# BLDC_MOTOR_TC264.net
KiCad netlist of a schematic drawn in Altium Designer
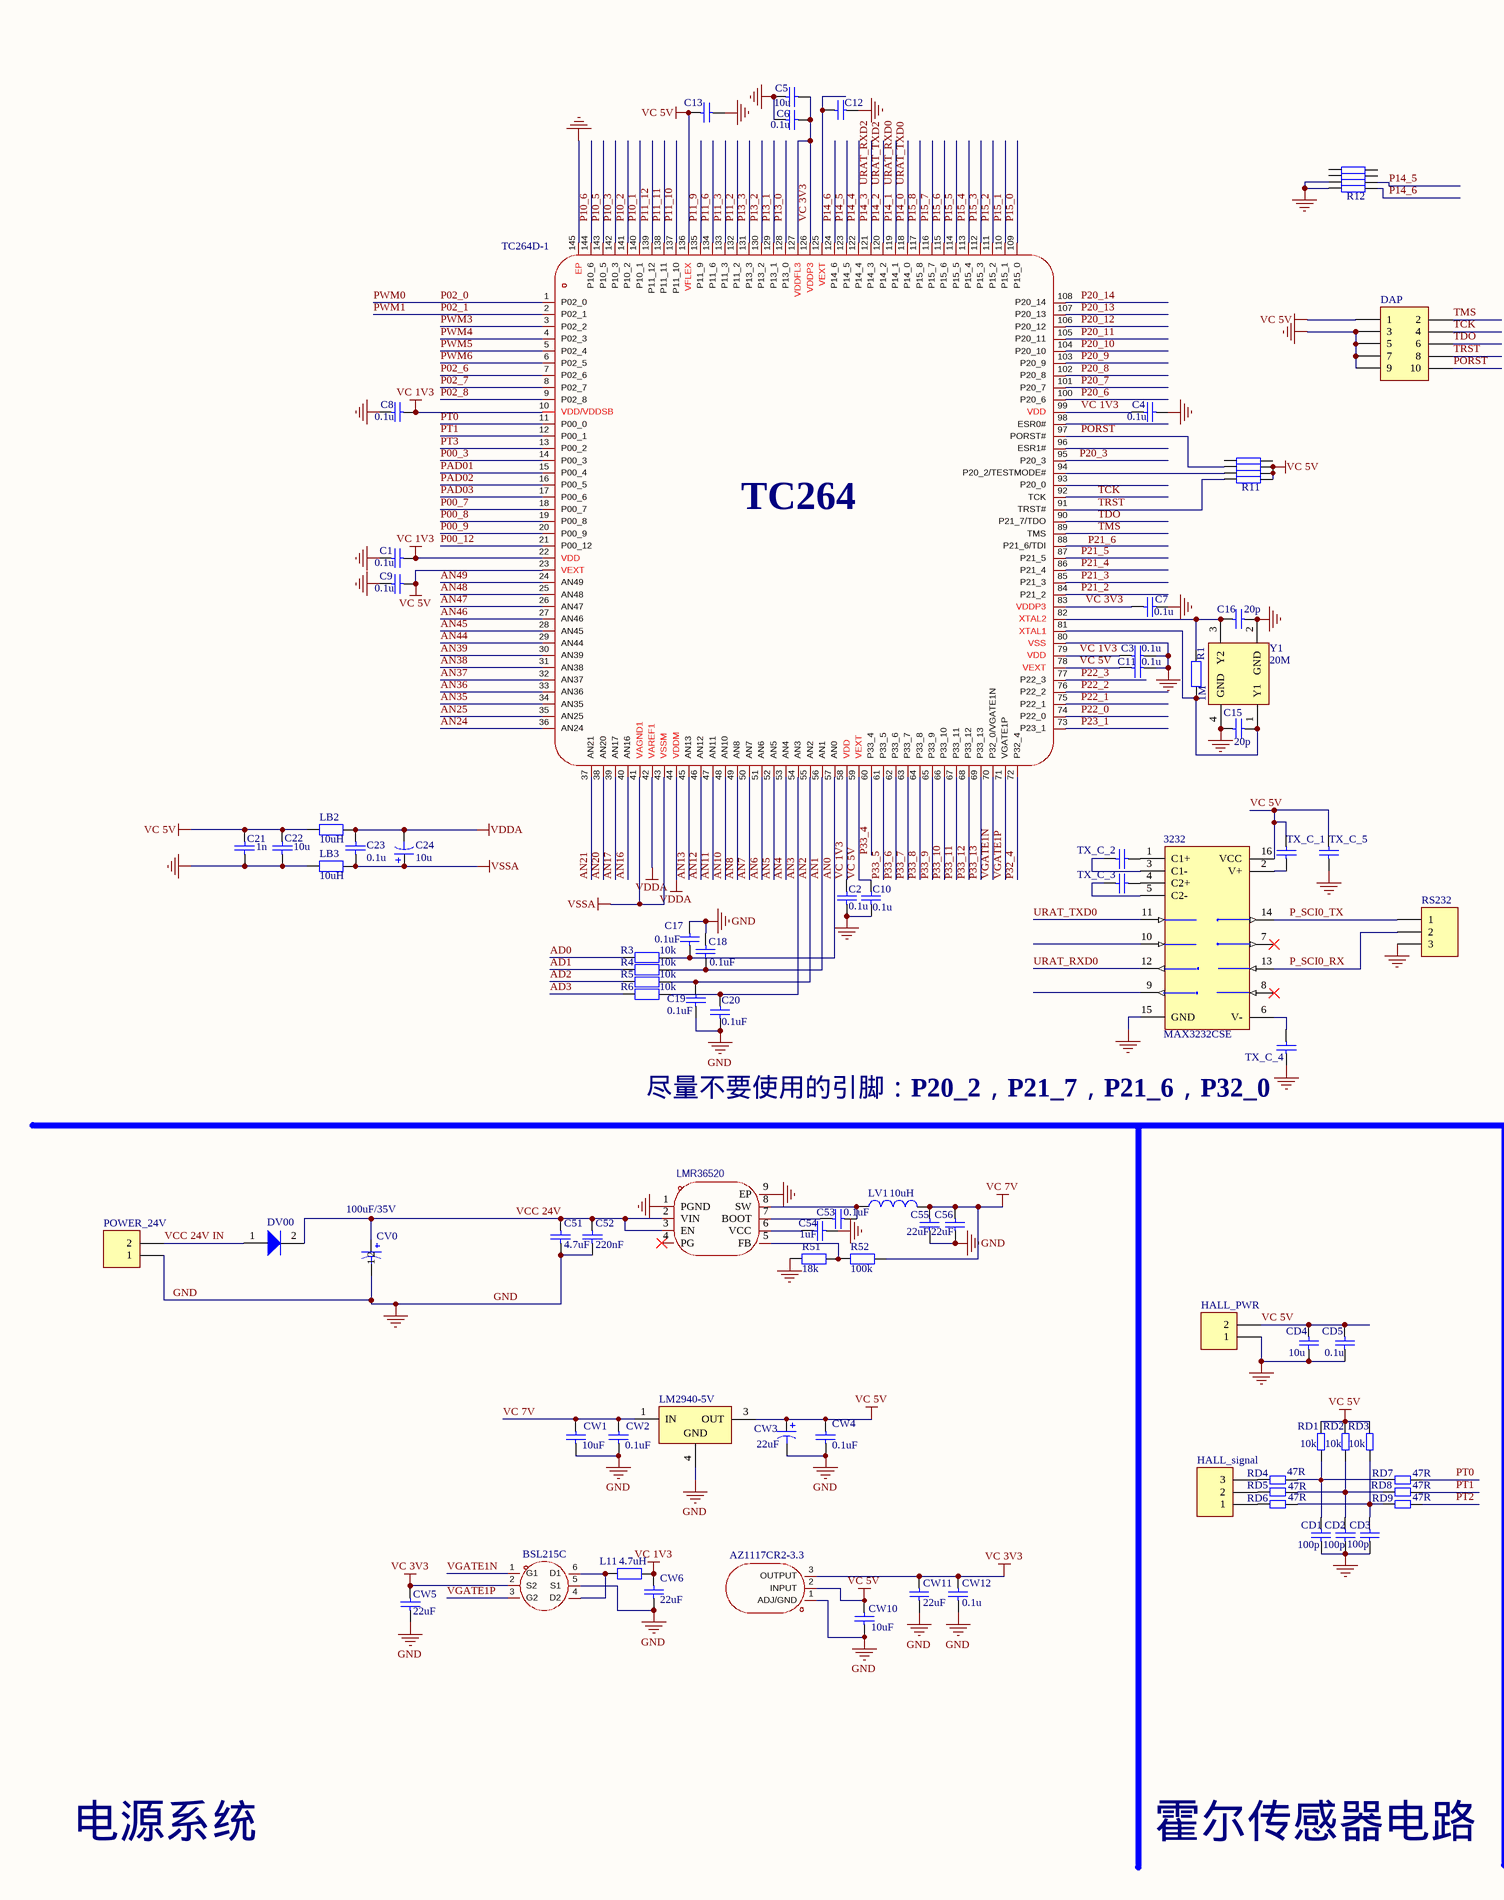
[diagram p0: BLDC_MOTOR_TC264.SCHDOC, left]
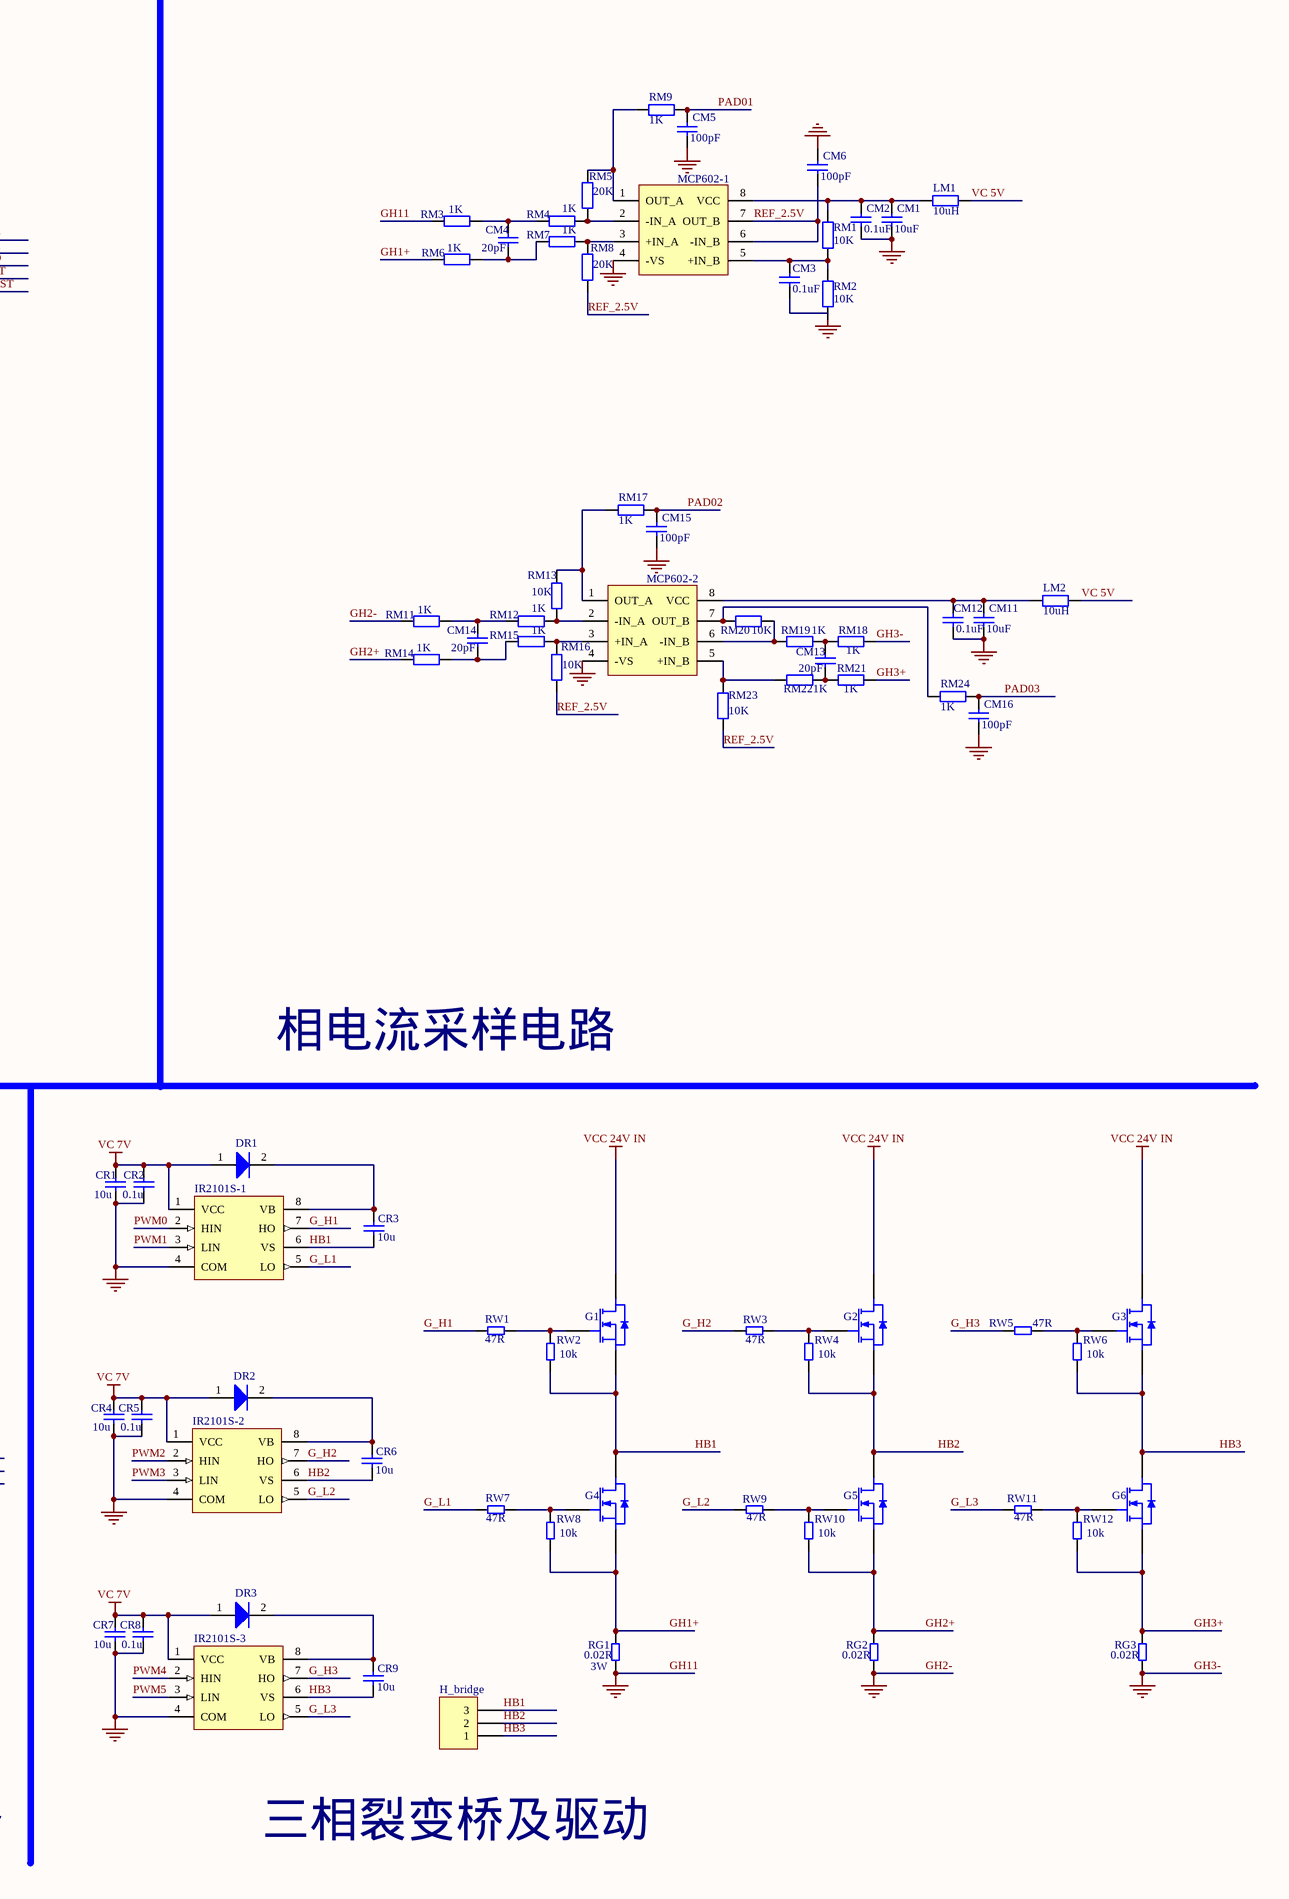
[diagram p1: BLDC_MOTOR_TC264.SCHDOC, right]

(export (version "E")
  (design (tool "Eeschema 10.0.6"))
  (components
    (comp (ref "3232")
      (value "MAX3232CSE")
      (footprint "LC-Standard-FootPrints-Protel99se-V1.01:LC-TSSOP-16")
      (description "3.0V TO 5.5V, Low-Power, up to 1Mbps, True RS-232 Transceiver Using Four 0.1礔 External Capacitor")
      (fields (field (name "PUBLISHER") "Altium Limited"))
      (libsource (lib "Maxim Communication Transceiver") (part "MAX3232CSE"))
    )
    (comp (ref "AZ1117CR2-3.3")
      (value "AZ1117CR2-3.3")
      (footprint "LC-SOT-89(SOT-89-3)")
      (libsource (lib "altium-import") (part "root_2_AZ1117CR2-3.3TRG1_"))
    )
    (comp (ref "BSL215C")
      (value "BSL215C")
      (footprint "LC-SOT-23-6")
      (libsource (lib "altium-import") (part "root_0_BSL215C_"))
    )
    (comp (ref "C1")
      (value "0.1u")
      (footprint "LC-0603_C")
      (description "Capacitor")
      (fields (field (name "PUBLISHER") "Altium Limited"))
      (libsource (lib "Miscellaneous Devices") (part "Cap"))
    )
    (comp (ref "C2")
      (value "0.1u")
      (footprint "LC-0603_C")
      (description "Capacitor")
      (fields (field (name "PUBLISHER") "Altium Limited"))
      (libsource (lib "Miscellaneous Devices") (part "Cap"))
    )
    (comp (ref "C3")
      (value "0.1u")
      (footprint "LC-0603_C")
      (description "Capacitor")
      (fields (field (name "PUBLISHER") "Altium Limited"))
      (libsource (lib "Miscellaneous Devices") (part "Cap"))
    )
    (comp (ref "C4")
      (value "0.1u")
      (footprint "LC-0603_C")
      (description "Capacitor")
      (fields (field (name "PUBLISHER") "Altium Limited"))
      (libsource (lib "Miscellaneous Devices") (part "Cap"))
    )
    (comp (ref "C5")
      (value "10u")
      (footprint "LC-0603_C")
      (description "Capacitor")
      (fields (field (name "PUBLISHER") "Altium Limited"))
      (libsource (lib "Miscellaneous Devices") (part "Cap"))
    )
    (comp (ref "C6")
      (value "0.1u")
      (footprint "LC-0603_C")
      (description "Capacitor")
      (fields (field (name "PUBLISHER") "Altium Limited"))
      (libsource (lib "Miscellaneous Devices") (part "Cap"))
    )
    (comp (ref "C7")
      (value "0.1u")
      (footprint "LC-0603_C")
      (description "Capacitor")
      (fields (field (name "PUBLISHER") "Altium Limited"))
      (libsource (lib "Miscellaneous Devices") (part "Cap"))
    )
    (comp (ref "C8")
      (value "0.1u")
      (footprint "LC-0603_C")
      (description "Capacitor")
      (fields (field (name "PUBLISHER") "Altium Limited"))
      (libsource (lib "Miscellaneous Devices") (part "Cap"))
    )
    (comp (ref "C9")
      (value "0.1u")
      (footprint "LC-0603_C")
      (description "Capacitor")
      (fields (field (name "PUBLISHER") "Altium Limited"))
      (libsource (lib "Miscellaneous Devices") (part "Cap"))
    )
    (comp (ref "C10")
      (value "0.1u")
      (footprint "LC-0603_C")
      (description "Capacitor")
      (fields (field (name "PUBLISHER") "Altium Limited"))
      (libsource (lib "Miscellaneous Devices") (part "Cap"))
    )
    (comp (ref "C11")
      (value "0.1u")
      (footprint "LC-0603_C")
      (description "Capacitor")
      (fields (field (name "PUBLISHER") "Altium Limited"))
      (libsource (lib "Miscellaneous Devices") (part "Cap"))
    )
    (comp (ref "C12")
      (value "0.1u")
      (footprint "LC-0603_C")
      (description "Capacitor")
      (fields (field (name "PUBLISHER") "Altium Limited"))
      (libsource (lib "Miscellaneous Devices") (part "Cap"))
    )
    (comp (ref "C13")
      (value "0.1u")
      (footprint "LC-0603_C")
      (description "Capacitor")
      (fields (field (name "PUBLISHER") "Altium Limited"))
      (libsource (lib "Miscellaneous Devices") (part "Cap"))
    )
    (comp (ref "C15")
      (value "20p")
      (footprint "LC-Standard-FootPrints-Protel99se-V1.01:LC-0603_C")
      (description "Capacitor")
      (fields (field (name "PUBLISHER") "Altium Limited"))
      (libsource (lib "Miscellaneous Devices") (part "Cap"))
    )
    (comp (ref "C16")
      (value "20p")
      (footprint "LC-Standard-FootPrints-Protel99se-V1.01:LC-0603_C")
      (description "Capacitor")
      (fields (field (name "PUBLISHER") "Altium Limited"))
      (libsource (lib "Miscellaneous Devices") (part "Cap"))
    )
    (comp (ref "C17")
      (value "0.1uF")
      (footprint "LC-Standard-FootPrints-Protel99se-V1.01:LC-0603_C")
      (description "Capacitor")
      (fields (field (name "PUBLISHER") "Altium Limited"))
      (libsource (lib "Miscellaneous Devices") (part "Cap"))
    )
    (comp (ref "C18")
      (value "0.1uF")
      (footprint "LC-Standard-FootPrints-Protel99se-V1.01:LC-0603_C")
      (description "Capacitor")
      (fields (field (name "PUBLISHER") "Altium Limited"))
      (libsource (lib "Miscellaneous Devices") (part "Cap"))
    )
    (comp (ref "C19")
      (value "0.1uF")
      (footprint "LC-Standard-FootPrints-Protel99se-V1.01:LC-0603_C")
      (description "Capacitor")
      (fields (field (name "PUBLISHER") "Altium Limited"))
      (libsource (lib "Miscellaneous Devices") (part "Cap"))
    )
    (comp (ref "C20")
      (value "0.1uF")
      (footprint "LC-Standard-FootPrints-Protel99se-V1.01:LC-0603_C")
      (description "Capacitor")
      (fields (field (name "PUBLISHER") "Altium Limited"))
      (libsource (lib "Miscellaneous Devices") (part "Cap"))
    )
    (comp (ref "C21")
      (value "1n")
      (footprint "LC-Standard-FootPrints-Protel99se-V1.01:LC-0603_C")
      (description "Capacitor")
      (fields (field (name "PUBLISHER") "Altium Limited"))
      (libsource (lib "Miscellaneous Devices") (part "Cap"))
    )
    (comp (ref "C22")
      (value "10u")
      (footprint "LC-Standard-FootPrints-Protel99se-V1.01:LC-0603_C")
      (description "Capacitor")
      (fields (field (name "PUBLISHER") "Altium Limited"))
      (libsource (lib "Miscellaneous Devices") (part "Cap"))
    )
    (comp (ref "C23")
      (value "0.1u")
      (footprint "LC-Standard-FootPrints-Protel99se-V1.01:LC-0603_C")
      (description "Capacitor")
      (fields (field (name "PUBLISHER") "Altium Limited"))
      (libsource (lib "Miscellaneous Devices") (part "Cap"))
    )
    (comp (ref "C24")
      (value "10u")
      (footprint "LC-0603_C")
      (description "Polarized Capacitor (Radial)")
      (fields (field (name "PUBLISHER") "Altium Limited"))
      (libsource (lib "Miscellaneous Devices") (part "Cap Pol1"))
    )
    (comp (ref "C51")
      (value "4.7uF")
      (footprint "LC-0805_C")
      (description "Capacitor")
      (fields (field (name "PUBLISHER") "Altium Limited"))
      (libsource (lib "Miscellaneous Devices") (part "Cap"))
    )
    (comp (ref "C52")
      (value "220nF")
      (footprint "LC-0805_C")
      (description "Capacitor")
      (fields (field (name "PUBLISHER") "Altium Limited"))
      (libsource (lib "Miscellaneous Devices") (part "Cap"))
    )
    (comp (ref "C53")
      (value "0.1uF")
      (footprint "LC-0603_C")
      (description "Capacitor")
      (fields (field (name "PUBLISHER") "Altium Limited"))
      (libsource (lib "Miscellaneous Devices") (part "Cap"))
    )
    (comp (ref "C54")
      (value "1uF")
      (footprint "LC-0603_C")
      (description "Capacitor")
      (fields (field (name "PUBLISHER") "Altium Limited"))
      (libsource (lib "Miscellaneous Devices") (part "Cap"))
    )
    (comp (ref "C55")
      (value "22uF")
      (footprint "LC-0805_C")
      (description "Capacitor")
      (fields (field (name "PUBLISHER") "Altium Limited"))
      (libsource (lib "Miscellaneous Devices") (part "Cap"))
    )
    (comp (ref "C56")
      (value "22uF")
      (footprint "LC-0805_C")
      (description "Capacitor")
      (fields (field (name "PUBLISHER") "Altium Limited"))
      (libsource (lib "Miscellaneous Devices") (part "Cap"))
    )
    (comp (ref "CD1")
      (value "100p")
      (footprint "LC-0805_C")
      (description "Capacitor")
      (fields (field (name "PUBLISHER") "Altium Limited"))
      (libsource (lib "Miscellaneous Devices") (part "Cap"))
    )
    (comp (ref "CD2")
      (value "100p")
      (footprint "LC-0805_C")
      (description "Capacitor")
      (fields (field (name "PUBLISHER") "Altium Limited"))
      (libsource (lib "Miscellaneous Devices") (part "Cap"))
    )
    (comp (ref "CD3")
      (value "100p")
      (footprint "LC-0805_C")
      (description "Capacitor")
      (fields (field (name "PUBLISHER") "Altium Limited"))
      (libsource (lib "Miscellaneous Devices") (part "Cap"))
    )
    (comp (ref "CD4")
      (value "10u")
      (footprint "LC-0805_C")
      (description "Capacitor")
      (fields (field (name "PUBLISHER") "Altium Limited"))
      (libsource (lib "Miscellaneous Devices") (part "Cap"))
    )
    (comp (ref "CD5")
      (value "0.1u")
      (footprint "LC-0805_C")
      (description "Capacitor")
      (fields (field (name "PUBLISHER") "Altium Limited"))
      (libsource (lib "Miscellaneous Devices") (part "Cap"))
    )
    (comp (ref "CM1")
      (value "10uF")
      (footprint "LC-0805_C")
      (description "Capacitor")
      (fields (field (name "Comment") "10u") (field (name "PUBLISHER") "Altium Limited"))
      (libsource (lib "Miscellaneous Devices") (part "Cap"))
    )
    (comp (ref "CM2")
      (value "0.1uF")
      (footprint "LC-0805_C")
      (description "Capacitor")
      (fields (field (name "Comment") "Cap") (field (name "PUBLISHER") "Altium Limited"))
      (libsource (lib "Miscellaneous Devices") (part "Cap"))
    )
    (comp (ref "CM3")
      (value "0.1uF")
      (footprint "0805")
      (description "Capacitor")
      (fields (field (name "Comment") "Cap") (field (name "PUBLISHER") "Altium Limited"))
      (libsource (lib "Miscellaneous Devices") (part "Cap"))
    )
    (comp (ref "CM4")
      (value "20pF")
      (footprint "LC-0805_C")
      (description "Capacitor")
      (fields (field (name "Comment") "Cap") (field (name "PUBLISHER") "Altium Limited"))
      (libsource (lib "Miscellaneous Devices") (part "Cap"))
    )
    (comp (ref "CM5")
      (value "100pF")
      (footprint "LC-0805_C")
      (description "Capacitor")
      (fields (field (name "Comment") "Cap") (field (name "PUBLISHER") "Altium Limited"))
      (libsource (lib "Miscellaneous Devices") (part "Cap"))
    )
    (comp (ref "CM6")
      (value "100pF")
      (footprint "LC-0805_C")
      (description "Capacitor")
      (fields (field (name "Comment") "Cap") (field (name "PUBLISHER") "Altium Limited"))
      (libsource (lib "Miscellaneous Devices") (part "Cap"))
    )
    (comp (ref "CM11")
      (value "10uF")
      (footprint "LC-0805_C")
      (description "Capacitor")
      (fields (field (name "Comment") "10u") (field (name "PUBLISHER") "Altium Limited"))
      (libsource (lib "Miscellaneous Devices") (part "Cap"))
    )
    (comp (ref "CM12")
      (value "0.1uF")
      (footprint "LC-0805_C")
      (description "Capacitor")
      (fields (field (name "Comment") "Cap") (field (name "PUBLISHER") "Altium Limited"))
      (libsource (lib "Miscellaneous Devices") (part "Cap"))
    )
    (comp (ref "CM13")
      (value "20pF")
      (footprint "LC-0805_C")
      (description "Capacitor")
      (fields (field (name "Comment") "Cap") (field (name "PUBLISHER") "Altium Limited"))
      (libsource (lib "Miscellaneous Devices") (part "Cap"))
    )
    (comp (ref "CM14")
      (value "20pF")
      (footprint "LC-0805_C")
      (description "Capacitor")
      (fields (field (name "Comment") "Cap") (field (name "PUBLISHER") "Altium Limited"))
      (libsource (lib "Miscellaneous Devices") (part "Cap"))
    )
    (comp (ref "CM15")
      (value "100pF")
      (footprint "LC-0805_C")
      (description "Capacitor")
      (fields (field (name "Comment") "Cap") (field (name "PUBLISHER") "Altium Limited"))
      (libsource (lib "Miscellaneous Devices") (part "Cap"))
    )
    (comp (ref "CM16")
      (value "100pF")
      (footprint "LC-0805_C")
      (description "Capacitor")
      (fields (field (name "PUBLISHER") "Altium Limited"))
      (libsource (lib "Miscellaneous Devices") (part "Cap"))
    )
    (comp (ref "CR1")
      (value "10u")
      (footprint "LC-0805_C")
      (description "Capacitor")
      (fields (field (name "PUBLISHER") "Altium Limited"))
      (libsource (lib "Miscellaneous Devices") (part "Cap"))
    )
    (comp (ref "CR2")
      (value "0.1u")
      (footprint "LC-0805_C")
      (description "Capacitor")
      (fields (field (name "PUBLISHER") "Altium Limited"))
      (libsource (lib "Miscellaneous Devices") (part "Cap"))
    )
    (comp (ref "CR3")
      (value "10u")
      (footprint "LC-1206_C")
      (description "Capacitor")
      (fields (field (name "PUBLISHER") "Altium Limited"))
      (libsource (lib "Miscellaneous Devices") (part "Cap"))
    )
    (comp (ref "CR4")
      (value "10u")
      (footprint "LC-0805_C")
      (description "Capacitor")
      (fields (field (name "PUBLISHER") "Altium Limited"))
      (libsource (lib "Miscellaneous Devices") (part "Cap"))
    )
    (comp (ref "CR5")
      (value "0.1u")
      (footprint "LC-0805_C")
      (description "Capacitor")
      (fields (field (name "PUBLISHER") "Altium Limited"))
      (libsource (lib "Miscellaneous Devices") (part "Cap"))
    )
    (comp (ref "CR6")
      (value "10u")
      (footprint "LC-1206_C")
      (description "Capacitor")
      (fields (field (name "PUBLISHER") "Altium Limited"))
      (libsource (lib "Miscellaneous Devices") (part "Cap"))
    )
    (comp (ref "CR7")
      (value "10u")
      (footprint "LC-0805_C")
      (description "Capacitor")
      (fields (field (name "PUBLISHER") "Altium Limited"))
      (libsource (lib "Miscellaneous Devices") (part "Cap"))
    )
    (comp (ref "CR8")
      (value "0.1u")
      (footprint "LC-0805_C")
      (description "Capacitor")
      (fields (field (name "PUBLISHER") "Altium Limited"))
      (libsource (lib "Miscellaneous Devices") (part "Cap"))
    )
    (comp (ref "CR9")
      (value "10u")
      (footprint "LC-1206_C")
      (description "Capacitor")
      (fields (field (name "PUBLISHER") "Altium Limited"))
      (libsource (lib "Miscellaneous Devices") (part "Cap"))
    )
    (comp (ref "CV0")
      (value "100uF/35V")
      (footprint "LIANGJICHAO_LIBRARY:CAP_SMD_8*10.2")
      (description "Polarized Capacitor (Radial)")
      (fields (field (name "Comment") "Cap Pol1") (field (name "PUBLISHER") "Altium Limited"))
      (libsource (lib "") (part "Cap Pol1_1"))
    )
    (comp (ref "CW1")
      (value "10uF")
      (footprint "LC-0603_C")
      (description "Capacitor")
      (fields (field (name "PUBLISHER") "Altium Limited"))
      (libsource (lib "Miscellaneous Devices") (part "Cap"))
    )
    (comp (ref "CW2")
      (value "0.1uF")
      (footprint "LC-0603_C")
      (description "Capacitor")
      (fields (field (name "Comment") "0.1u") (field (name "PUBLISHER") "Altium Limited"))
      (libsource (lib "Miscellaneous Devices") (part "Cap"))
    )
    (comp (ref "CW3")
      (value "22uF")
      (footprint "LC-0805_C")
      (description "Polarized Capacitor (Radial)")
      (fields (field (name "PUBLISHER") "Altium Limited"))
      (libsource (lib "Miscellaneous Devices") (part "Cap Pol1"))
    )
    (comp (ref "CW4")
      (value "0.1uF")
      (footprint "LC-0603_C")
      (description "Capacitor")
      (fields (field (name "Comment") "0.1u") (field (name "PUBLISHER") "Altium Limited"))
      (libsource (lib "Miscellaneous Devices") (part "Cap"))
    )
    (comp (ref "CW5")
      (value "22uF")
      (footprint "LC-0603_C")
      (description "Capacitor")
      (fields (field (name "PUBLISHER") "Altium Limited"))
      (libsource (lib "Miscellaneous Devices") (part "Cap"))
    )
    (comp (ref "CW6")
      (value "22uF")
      (footprint "LC-0603_C")
      (description "Capacitor")
      (fields (field (name "PUBLISHER") "Altium Limited"))
      (libsource (lib "Miscellaneous Devices") (part "Cap"))
    )
    (comp (ref "CW10")
      (value "10uF")
      (footprint "LC-0603_C")
      (description "Capacitor")
      (fields (field (name "PUBLISHER") "Altium Limited"))
      (libsource (lib "Miscellaneous Devices") (part "Cap"))
    )
    (comp (ref "CW11")
      (value "22uF")
      (footprint "LC-0603_C")
      (description "Capacitor")
      (fields (field (name "PUBLISHER") "Altium Limited"))
      (libsource (lib "Miscellaneous Devices") (part "Cap"))
    )
    (comp (ref "CW12")
      (value "0.1u")
      (footprint "LC-0603_C")
      (description "Capacitor")
      (fields (field (name "PUBLISHER") "Altium Limited"))
      (libsource (lib "Miscellaneous Devices") (part "Cap"))
    )
    (comp (ref "DAP")
      (value "Header 5X2")
      (footprint "HDR2X5")
      (description "Header, 5-Pin, Dual row")
      (fields (field (name "PUBLISHER") "Altium Limited"))
      (libsource (lib "Miscellaneous Connectors") (part "Header 5X2"))
    )
    (comp (ref "DR1")
      (value "C84635")
      (footprint "LC-SMA(DO-214AC)_S2")
      (description "Default Diode")
      (fields (field (name "PUBLISHER") "Altium Limited"))
      (libsource (lib "Miscellaneous Devices") (part "Diode"))
    )
    (comp (ref "DR2")
      (value "C84635")
      (footprint "LC-SMA(DO-214AC)_S2")
      (description "Default Diode")
      (fields (field (name "PUBLISHER") "Altium Limited"))
      (libsource (lib "Miscellaneous Devices") (part "Diode"))
    )
    (comp (ref "DR3")
      (value "C84635")
      (footprint "LC-SMA(DO-214AC)_S2")
      (description "Default Diode")
      (fields (field (name "PUBLISHER") "Altium Limited"))
      (libsource (lib "Miscellaneous Devices") (part "Diode"))
    )
    (comp (ref "DV00")
      (value "C35722")
      (footprint "LC-SMA(DO-214AC)_S5")
      (description "Default Diode")
      (fields (field (name "PUBLISHER") "Altium Limited"))
      (libsource (lib "Miscellaneous Devices") (part "Diode"))
    )
    (comp (ref "G1") (value "BUK9222") (footprint "TO-252-2") (libsource (lib "liang_SCH") (part "MOSFET_N")))
    (comp (ref "G2") (value "BUK9222") (footprint "TO-252-2") (libsource (lib "liang_SCH") (part "MOSFET_N")))
    (comp (ref "G3") (value "BUK9222") (footprint "TO-252-2") (libsource (lib "liang_SCH") (part "MOSFET_N")))
    (comp (ref "G4") (value "BUK9222") (footprint "TO-252-2") (libsource (lib "liang_SCH") (part "MOSFET_N")))
    (comp (ref "G5") (value "BUK9222") (footprint "TO-252-2") (libsource (lib "liang_SCH") (part "MOSFET_N")))
    (comp (ref "G6") (value "BUK9222") (footprint "TO-252-2") (libsource (lib "liang_SCH") (part "MOSFET_N")))
    (comp (ref "HALL_PWR")
      (value "~")
      (footprint "KF128-jiexian_2P")
      (description "Header, 2-Pin")
      (fields (field (name "PUBLISHER") "Altium Limited"))
      (libsource (lib "Miscellaneous Connectors") (part "Header 2"))
    )
    (comp (ref "HALL_signal")
      (value "Header 3")
      (footprint "kf128_duanzi_3P")
      (description "Header, 3-Pin")
      (fields (field (name "PUBLISHER") "Altium Limited"))
      (libsource (lib "") (part "Header 3_1"))
    )
    (comp (ref "H_bridge")
      (value "Header 3")
      (footprint "kf128_duanzi_3P")
      (description "Header, 3-Pin")
      (fields (field (name "PUBLISHER") "Altium Limited"))
      (libsource (lib "") (part "Header 3_1"))
    )
    (comp (ref "IR2101S-1")
      (value "IR2101")
      (footprint "LC-SOIC-8_150mil")
      (libsource (lib "liang_SCH") (part "IR2101"))
    )
    (comp (ref "IR2101S-2")
      (value "IR2101")
      (footprint "LC-SOIC-8_150mil")
      (libsource (lib "liang_SCH") (part "IR2101"))
    )
    (comp (ref "IR2101S-3")
      (value "IR2101")
      (footprint "LC-SOIC-8_150mil")
      (libsource (lib "liang_SCH") (part "IR2101"))
    )
    (comp (ref "L11")
      (value "4.7uH")
      (footprint "LIANGJICHAO_LIBRARY:L0806")
      (description "Resistor")
      (fields (field (name "PUBLISHER") "Altium Limited"))
      (libsource (lib "") (part "Res2_3"))
    )
    (comp (ref "LB2")
      (value "10uH")
      (footprint "LC-Standard-FootPrints-Protel99se-V1.01:LC-1206_L")
      (description "Resistor")
      (fields (field (name "Comment") "C1051") (field (name "PUBLISHER") "Altium Limited"))
      (libsource (lib "") (part "Res2_1"))
    )
    (comp (ref "LB3")
      (value "10uH")
      (footprint "LC-Standard-FootPrints-Protel99se-V1.01:LC-1206_L")
      (description "Resistor")
      (fields (field (name "Comment") "C1051") (field (name "PUBLISHER") "Altium Limited"))
      (libsource (lib "") (part "Res2_1"))
    )
    (comp (ref "LM1")
      (value "10uH")
      (footprint "LC-0805_L")
      (description "Resistor")
      (fields (field (name "PUBLISHER") "Altium Limited"))
      (libsource (lib "") (part "Res2_1"))
    )
    (comp (ref "LM2")
      (value "10uH")
      (footprint "LC-0805_L")
      (description "Resistor")
      (fields (field (name "PUBLISHER") "Altium Limited"))
      (libsource (lib "") (part "Res2_1"))
    )
    (comp (ref "LM2940-5V")
      (value "LM2940")
      (footprint "LC-SOT-223")
      (description "Precision 1A Regulator")
      (fields (field (name "PUBLISHER") "Altium Limited"))
      (libsource (lib "ST Power Mgt Voltage Regulator") (part "L7805ABD2T"))
    )
    (comp (ref "LMR36520")
      (value "LMR36520FADDAR")
      (footprint "LC-SOIC-8_EP_150mil")
      (fields (field (name "MANUFACTURER") "TI(德州仪器)"))
      (libsource (lib "altium-import") (part "root_0_LMR36520FADDAR_"))
    )
    (comp (ref "LV1")
      (value "10uH")
      (footprint "LIANGJICHAO_LIBRARY:SMD_0650")
      (description "Inductor")
      (fields (field (name "PUBLISHER") "Altium Limited"))
      (libsource (lib "Miscellaneous Devices") (part "Inductor"))
    )
    (comp (ref "MCP602-1")
      (value "LM258")
      (footprint "SOP8_555_lm393")
      (libsource (lib "liang_SCH") (part "LM258"))
    )
    (comp (ref "MCP602-2")
      (value "LM258")
      (footprint "SOP8_555_lm393")
      (libsource (lib "liang_SCH") (part "LM258"))
    )
    (comp (ref "POWER_24V")
      (value "Header 2")
      (footprint "KF128-jiexian_2P")
      (description "Header, 2-Pin")
      (fields (field (name "PUBLISHER") "Altium Limited"))
      (libsource (lib "Miscellaneous Connectors") (part "Header 2"))
    )
    (comp (ref "R1")
      (value "1M")
      (footprint "LC-Standard-FootPrints-Protel99se-V1.01:LC-0603_R")
      (description "Resistor")
      (fields (field (name "PUBLISHER") "Altium Limited"))
      (libsource (lib "") (part "Res2_2"))
    )
    (comp (ref "R3")
      (value "10k")
      (footprint "LC-Standard-FootPrints-Protel99se-V1.01:LC-0603_R")
      (description "Resistor")
      (fields (field (name "PUBLISHER") "Altium Limited"))
      (libsource (lib "") (part "Res2_3"))
    )
    (comp (ref "R4")
      (value "10k")
      (footprint "LC-Standard-FootPrints-Protel99se-V1.01:LC-0603_R")
      (description "Resistor")
      (fields (field (name "PUBLISHER") "Altium Limited"))
      (libsource (lib "") (part "Res2_3"))
    )
    (comp (ref "R5")
      (value "10k")
      (footprint "LC-Standard-FootPrints-Protel99se-V1.01:LC-0603_R")
      (description "Resistor")
      (fields (field (name "PUBLISHER") "Altium Limited"))
      (libsource (lib "") (part "Res2_3"))
    )
    (comp (ref "R6")
      (value "10k")
      (footprint "LC-Standard-FootPrints-Protel99se-V1.01:LC-0603_R")
      (description "Resistor")
      (fields (field (name "PUBLISHER") "Altium Limited"))
      (libsource (lib "") (part "Res2_3"))
    )
    (comp (ref "R11")
      (value "10k")
      (footprint "LC-0603_Rx4")
      (libsource (lib "liang_SCH") (part "RES_RANGE_4"))
    )
    (comp (ref "R12")
      (value "47k")
      (footprint "LC-0603_Rx4")
      (libsource (lib "liang_SCH") (part "RES_RANGE_4"))
    )
    (comp (ref "R51")
      (value "18k")
      (footprint "LC-0603_R")
      (description "Resistor")
      (fields (field (name "PUBLISHER") "Altium Limited"))
      (libsource (lib "") (part "Res2_1"))
    )
    (comp (ref "R52")
      (value "100k")
      (footprint "LC-0603_R")
      (description "Resistor")
      (fields (field (name "PUBLISHER") "Altium Limited"))
      (libsource (lib "") (part "Res2_1"))
    )
    (comp (ref "RD1") (value "10k") (footprint "LC-0805_R") (libsource (lib "") (part "RES_COMMOM_2")))
    (comp (ref "RD2") (value "10k") (footprint "LC-0805_R") (libsource (lib "") (part "RES_COMMOM_2")))
    (comp (ref "RD3")
      (value "10k")
      (footprint "LC-Standard-FootPrints-Protel99se-V1.01:LC-0805_R")
      (libsource (lib "") (part "RES_COMMOM_2"))
    )
    (comp (ref "RD4") (value "47R") (footprint "LC-0805_R") (libsource (lib "liang_SCH") (part "RES_COMMOM")))
    (comp (ref "RD5") (value "47R") (footprint "LC-0805_R") (libsource (lib "liang_SCH") (part "RES_COMMOM")))
    (comp (ref "RD6")
      (value "47R")
      (footprint "LC-Standard-FootPrints-Protel99se-V1.01:LC-0805_R")
      (libsource (lib "liang_SCH") (part "RES_COMMOM"))
    )
    (comp (ref "RD7") (value "47R") (footprint "LC-0805_R") (libsource (lib "liang_SCH") (part "RES_COMMOM")))
    (comp (ref "RD8") (value "47R") (footprint "LC-0805_R") (libsource (lib "liang_SCH") (part "RES_COMMOM")))
    (comp (ref "RD9")
      (value "47R")
      (footprint "LC-Standard-FootPrints-Protel99se-V1.01:LC-0805_R")
      (libsource (lib "liang_SCH") (part "RES_COMMOM"))
    )
    (comp (ref "RG1")
      (value "0.02R")
      (footprint "LC-Standard-FootPrints-Protel99se-V1.01:LC-2512_R")
      (libsource (lib "") (part "RES_COMMOM_2"))
    )
    (comp (ref "RG2")
      (value "0.02R")
      (footprint "LC-Standard-FootPrints-Protel99se-V1.01:LC-2512_R")
      (libsource (lib "") (part "RES_COMMOM_2"))
    )
    (comp (ref "RG3")
      (value "0.02R")
      (footprint "LC-Standard-FootPrints-Protel99se-V1.01:LC-2512_R")
      (libsource (lib "") (part "RES_COMMOM_2"))
    )
    (comp (ref "RM1")
      (value "10K")
      (footprint "LC-0805_R")
      (description "Resistor")
      (fields (field (name "Comment") "Res2") (field (name "PUBLISHER") "Altium Limited"))
      (libsource (lib "") (part "Res2_2"))
    )
    (comp (ref "RM2")
      (value "10K")
      (footprint "LC-0805_R")
      (description "Resistor")
      (fields (field (name "Comment") "Res2") (field (name "PUBLISHER") "Altium Limited"))
      (libsource (lib "") (part "Res2_2"))
    )
    (comp (ref "RM3")
      (value "1K")
      (footprint "LC-0805_R")
      (description "Resistor")
      (fields (field (name "Comment") "Res2") (field (name "PUBLISHER") "Altium Limited"))
      (libsource (lib "") (part "Res2_1"))
    )
    (comp (ref "RM4")
      (value "1K")
      (footprint "LC-0805_R")
      (description "Resistor")
      (fields (field (name "Comment") "Res2") (field (name "PUBLISHER") "Altium Limited"))
      (libsource (lib "") (part "Res2_1"))
    )
    (comp (ref "RM5")
      (value "20K")
      (footprint "LC-0805_R")
      (description "Resistor")
      (fields (field (name "Comment") "Res2") (field (name "PUBLISHER") "Altium Limited"))
      (libsource (lib "Miscellaneous Devices") (part "Res2"))
    )
    (comp (ref "RM6")
      (value "1K")
      (footprint "LC-0805_R")
      (description "Resistor")
      (fields (field (name "Comment") "Res2") (field (name "PUBLISHER") "Altium Limited"))
      (libsource (lib "") (part "Res2_1"))
    )
    (comp (ref "RM7")
      (value "1K")
      (footprint "LC-0805_R")
      (description "Resistor")
      (fields (field (name "Comment") "Res2") (field (name "PUBLISHER") "Altium Limited"))
      (libsource (lib "") (part "Res2_1"))
    )
    (comp (ref "RM8")
      (value "20K")
      (footprint "LC-0805_R")
      (description "Resistor")
      (fields (field (name "Comment") "Res2") (field (name "PUBLISHER") "Altium Limited"))
      (libsource (lib "") (part "Res2_2"))
    )
    (comp (ref "RM9")
      (value "1K")
      (footprint "LC-0805_R")
      (description "Resistor")
      (fields (field (name "Comment") "Res2") (field (name "PUBLISHER") "Altium Limited"))
      (libsource (lib "") (part "Res2_1"))
    )
    (comp (ref "RM11")
      (value "1K")
      (footprint "LC-0805_R")
      (description "Resistor")
      (fields (field (name "Comment") "Res2") (field (name "PUBLISHER") "Altium Limited"))
      (libsource (lib "") (part "Res2_1"))
    )
    (comp (ref "RM12")
      (value "1K")
      (footprint "LC-0805_R")
      (description "Resistor")
      (fields (field (name "Comment") "Res2") (field (name "PUBLISHER") "Altium Limited"))
      (libsource (lib "") (part "Res2_1"))
    )
    (comp (ref "RM13")
      (value "10K")
      (footprint "LC-0805_R")
      (description "Resistor")
      (fields (field (name "Comment") "Res2") (field (name "PUBLISHER") "Altium Limited"))
      (libsource (lib "Miscellaneous Devices") (part "Res2"))
    )
    (comp (ref "RM14")
      (value "1K")
      (footprint "LC-0805_R")
      (description "Resistor")
      (fields (field (name "Comment") "Res2") (field (name "PUBLISHER") "Altium Limited"))
      (libsource (lib "") (part "Res2_1"))
    )
    (comp (ref "RM15")
      (value "1K")
      (footprint "LC-0805_R")
      (description "Resistor")
      (fields (field (name "Comment") "Res2") (field (name "PUBLISHER") "Altium Limited"))
      (libsource (lib "") (part "Res2_1"))
    )
    (comp (ref "RM16")
      (value "10K")
      (footprint "LC-0805_R")
      (description "Resistor")
      (fields (field (name "Comment") "Res2") (field (name "PUBLISHER") "Altium Limited"))
      (libsource (lib "") (part "Res2_2"))
    )
    (comp (ref "RM17")
      (value "1K")
      (footprint "LC-0805_R")
      (description "Resistor")
      (fields (field (name "Comment") "Res2") (field (name "PUBLISHER") "Altium Limited"))
      (libsource (lib "") (part "Res2_1"))
    )
    (comp (ref "RM18")
      (value "1K")
      (footprint "LC-0805_R")
      (description "Resistor")
      (fields (field (name "Comment") "Res2") (field (name "PUBLISHER") "Altium Limited"))
      (libsource (lib "") (part "Res2_3"))
    )
    (comp (ref "RM19")
      (value "1K")
      (footprint "LC-0805_R")
      (description "Resistor")
      (fields (field (name "Comment") "Res2") (field (name "PUBLISHER") "Altium Limited"))
      (libsource (lib "") (part "Res2_3"))
    )
    (comp (ref "RM20")
      (value "10K")
      (footprint "LC-0805_R")
      (description "Resistor")
      (fields (field (name "Comment") "Res2") (field (name "PUBLISHER") "Altium Limited"))
      (libsource (lib "") (part "Res2_1"))
    )
    (comp (ref "RM21")
      (value "1K")
      (footprint "LC-0805_R")
      (description "Resistor")
      (fields (field (name "Comment") "Res2") (field (name "PUBLISHER") "Altium Limited"))
      (libsource (lib "") (part "Res2_3"))
    )
    (comp (ref "RM22")
      (value "1K")
      (footprint "LC-0805_R")
      (description "Resistor")
      (fields (field (name "Comment") "Res2") (field (name "PUBLISHER") "Altium Limited"))
      (libsource (lib "") (part "Res2_3"))
    )
    (comp (ref "RM23")
      (value "10K")
      (footprint "LC-0805_R")
      (description "Resistor")
      (fields (field (name "Comment") "Res2") (field (name "PUBLISHER") "Altium Limited"))
      (libsource (lib "Miscellaneous Devices") (part "Res2"))
    )
    (comp (ref "RM24")
      (value "1K")
      (footprint "LC-0805_R")
      (description "Resistor")
      (fields (field (name "Comment") "Res2") (field (name "PUBLISHER") "Altium Limited"))
      (libsource (lib "") (part "Res2_1"))
    )
    (comp (ref "RS232")
      (value "Header 3")
      (footprint "kf128_duanzi_3P")
      (description "Header, 3-Pin")
      (fields (field (name "PUBLISHER") "Altium Limited"))
      (libsource (lib "Miscellaneous Connectors") (part "Header 3"))
    )
    (comp (ref "RW1") (value "47R") (footprint "0805") (libsource (lib "liang_SCH") (part "RES_COMMOM")))
    (comp (ref "RW2") (value "10k") (footprint "0805") (libsource (lib "") (part "RES_COMMOM_1")))
    (comp (ref "RW3") (value "47R") (footprint "0805") (libsource (lib "liang_SCH") (part "RES_COMMOM")))
    (comp (ref "RW4") (value "10k") (footprint "0805") (libsource (lib "") (part "RES_COMMOM_1")))
    (comp (ref "RW5") (value "47R") (footprint "0805") (libsource (lib "liang_SCH") (part "RES_COMMOM")))
    (comp (ref "RW6") (value "10k") (footprint "0805") (libsource (lib "") (part "RES_COMMOM_1")))
    (comp (ref "RW7") (value "47R") (footprint "0805") (libsource (lib "liang_SCH") (part "RES_COMMOM")))
    (comp (ref "RW8") (value "10k") (footprint "0805") (libsource (lib "") (part "RES_COMMOM_1")))
    (comp (ref "RW9") (value "47R") (footprint "0805") (libsource (lib "liang_SCH") (part "RES_COMMOM")))
    (comp (ref "RW10") (value "10k") (footprint "0805") (libsource (lib "") (part "RES_COMMOM_1")))
    (comp (ref "RW11") (value "47R") (footprint "0805") (libsource (lib "liang_SCH") (part "RES_COMMOM")))
    (comp (ref "RW12") (value "10k") (footprint "0805") (libsource (lib "") (part "RES_COMMOM_1")))
    (comp (ref "TC264D-1")
      (value "TC264D")
      (footprint "TC264D-LQFP144")
      (libsource (lib "liang_SCH") (part "TC264D"))
    )
    (comp (ref "TX_C_1")
      (value "0.1u")
      (footprint "LC-0603_C")
      (description "Capacitor")
      (fields (field (name "PUBLISHER") "Altium Limited"))
      (libsource (lib "Miscellaneous Devices") (part "Cap"))
    )
    (comp (ref "TX_C_2")
      (value "0.1u")
      (footprint "LC-Standard-FootPrints-Protel99se-V1.01:LC-0603_C")
      (description "Capacitor")
      (fields (field (name "PUBLISHER") "Altium Limited"))
      (libsource (lib "Miscellaneous Devices") (part "Cap"))
    )
    (comp (ref "TX_C_3")
      (value "0.1u")
      (footprint "LC-Standard-FootPrints-Protel99se-V1.01:LC-0603_C")
      (description "Capacitor")
      (fields (field (name "PUBLISHER") "Altium Limited"))
      (libsource (lib "Miscellaneous Devices") (part "Cap"))
    )
    (comp (ref "TX_C_4")
      (value "0.1u")
      (footprint "LC-Standard-FootPrints-Protel99se-V1.01:LC-0603_C")
      (description "Capacitor")
      (fields (field (name "PUBLISHER") "Altium Limited"))
      (libsource (lib "Miscellaneous Devices") (part "Cap"))
    )
    (comp (ref "TX_C_5")
      (value "0.1u")
      (footprint "LC-0603_C")
      (description "Capacitor")
      (fields (field (name "PUBLISHER") "Altium Limited"))
      (libsource (lib "Miscellaneous Devices") (part "Cap"))
    )
    (comp (ref "Y1")
      (value "20M")
      (footprint "LC-Standard-FootPrints-Protel99se-V1.01:LC-SMD-3225_4P")
      (libsource (lib "liang_SCH") (part "XTL-YXL"))
    )
  )
  (nets
    (net (code "1") (name "/AD0") (class "Default")
      (node (ref "R3") (pin "1") (pinfunction "1_1") (pintype "passive"))
    )
    (net (code "2") (name "/AD1") (class "Default")
      (node (ref "R4") (pin "1") (pinfunction "1_1") (pintype "passive"))
    )
    (net (code "3") (name "/AD2") (class "Default")
      (node (ref "R5") (pin "1") (pinfunction "1_1") (pintype "passive"))
    )
    (net (code "4") (name "/AD3") (class "Default")
      (node (ref "R6") (pin "1") (pinfunction "1_1") (pintype "passive"))
    )
    (net (code "5") (name "/AN0") (class "Default")
      (node (ref "C17") (pin "1") (pinfunction "1_1") (pintype "passive"))
      (node (ref "R3") (pin "2") (pinfunction "2_2") (pintype "passive"))
      (node (ref "TC264D-1") (pin "57") (pinfunction "AN0_57") (pintype "passive"))
    )
    (net (code "6") (name "/AN1") (class "Default")
      (node (ref "C18") (pin "1") (pinfunction "1_1") (pintype "passive"))
      (node (ref "R4") (pin "2") (pinfunction "2_2") (pintype "passive"))
      (node (ref "TC264D-1") (pin "56") (pinfunction "AN1_56") (pintype "passive"))
    )
    (net (code "7") (name "/AN2") (class "Default")
      (node (ref "C19") (pin "2") (pinfunction "2_2") (pintype "passive"))
      (node (ref "R5") (pin "2") (pinfunction "2_2") (pintype "passive"))
      (node (ref "TC264D-1") (pin "55") (pinfunction "AN2_55") (pintype "passive"))
    )
    (net (code "8") (name "/AN3") (class "Default")
      (node (ref "C20") (pin "2") (pinfunction "2_2") (pintype "passive"))
      (node (ref "R6") (pin "2") (pinfunction "2_2") (pintype "passive"))
      (node (ref "TC264D-1") (pin "54") (pinfunction "AN3_54") (pintype "passive"))
    )
    (net (code "9") (name "/AN4") (class "Default")
      (node (ref "TC264D-1") (pin "53") (pinfunction "AN4_53") (pintype "passive"))
    )
    (net (code "10") (name "/AN5") (class "Default")
      (node (ref "TC264D-1") (pin "52") (pinfunction "AN5_52") (pintype "passive"))
    )
    (net (code "11") (name "/AN6") (class "Default")
      (node (ref "TC264D-1") (pin "51") (pinfunction "AN6_51") (pintype "passive"))
    )
    (net (code "12") (name "/AN7") (class "Default")
      (node (ref "TC264D-1") (pin "50") (pinfunction "AN7_50") (pintype "passive"))
    )
    (net (code "13") (name "/AN8") (class "Default")
      (node (ref "TC264D-1") (pin "49") (pinfunction "AN8_49") (pintype "passive"))
    )
    (net (code "14") (name "/AN10") (class "Default")
      (node (ref "TC264D-1") (pin "48") (pinfunction "AN10_48") (pintype "passive"))
    )
    (net (code "15") (name "/AN11") (class "Default")
      (node (ref "TC264D-1") (pin "47") (pinfunction "AN11_47") (pintype "passive"))
    )
    (net (code "16") (name "/AN12") (class "Default")
      (node (ref "TC264D-1") (pin "46") (pinfunction "AN12_46") (pintype "passive"))
    )
    (net (code "17") (name "/AN13") (class "Default")
      (node (ref "TC264D-1") (pin "45") (pinfunction "AN13_45") (pintype "passive"))
    )
    (net (code "18") (name "/AN16") (class "Default")
      (node (ref "TC264D-1") (pin "40") (pinfunction "AN16_40") (pintype "passive"))
    )
    (net (code "19") (name "/AN17") (class "Default")
      (node (ref "TC264D-1") (pin "39") (pinfunction "AN17_39") (pintype "passive"))
    )
    (net (code "20") (name "/AN20") (class "Default")
      (node (ref "TC264D-1") (pin "38") (pinfunction "AN20_38") (pintype "passive"))
    )
    (net (code "21") (name "/AN21") (class "Default")
      (node (ref "TC264D-1") (pin "37") (pinfunction "AN21_37") (pintype "passive"))
    )
    (net (code "22") (name "/AN24") (class "Default")
      (node (ref "TC264D-1") (pin "36") (pinfunction "AN24_36") (pintype "passive"))
    )
    (net (code "23") (name "/AN25") (class "Default")
      (node (ref "TC264D-1") (pin "35") (pinfunction "AN25_35") (pintype "passive"))
    )
    (net (code "24") (name "/AN35") (class "Default")
      (node (ref "TC264D-1") (pin "34") (pinfunction "AN35_34") (pintype "passive"))
    )
    (net (code "25") (name "/AN36") (class "Default")
      (node (ref "TC264D-1") (pin "33") (pinfunction "AN36_33") (pintype "passive"))
    )
    (net (code "26") (name "/AN37") (class "Default")
      (node (ref "TC264D-1") (pin "32") (pinfunction "AN37_32") (pintype "passive"))
    )
    (net (code "27") (name "/AN38") (class "Default")
      (node (ref "TC264D-1") (pin "31") (pinfunction "AN38_31") (pintype "passive"))
    )
    (net (code "28") (name "/AN39") (class "Default")
      (node (ref "TC264D-1") (pin "30") (pinfunction "AN39_30") (pintype "passive"))
    )
    (net (code "29") (name "/AN44") (class "Default")
      (node (ref "TC264D-1") (pin "29") (pinfunction "AN44_29") (pintype "passive"))
    )
    (net (code "30") (name "/AN45") (class "Default")
      (node (ref "TC264D-1") (pin "28") (pinfunction "AN45_28") (pintype "passive"))
    )
    (net (code "31") (name "/AN46") (class "Default")
      (node (ref "TC264D-1") (pin "27") (pinfunction "AN46_27") (pintype "passive"))
    )
    (net (code "32") (name "/AN47") (class "Default")
      (node (ref "TC264D-1") (pin "26") (pinfunction "AN47_26") (pintype "passive"))
    )
    (net (code "33") (name "/AN48") (class "Default")
      (node (ref "TC264D-1") (pin "25") (pinfunction "AN48_25") (pintype "passive"))
    )
    (net (code "34") (name "/AN49") (class "Default")
      (node (ref "TC264D-1") (pin "24") (pinfunction "AN49_24") (pintype "passive"))
    )
    (net (code "35") (name "/GH1+") (class "Default")
      (node (ref "G4") (pin "3") (pinfunction "S_3") (pintype "passive"))
      (node (ref "RG1") (pin "1") (pinfunction "1_1") (pintype "passive"))
      (node (ref "RM6") (pin "2") (pinfunction "2_2") (pintype "passive"))
      (node (ref "RW8") (pin "1") (pinfunction "1_1") (pintype "passive"))
    )
    (net (code "36") (name "/GH2+") (class "Default")
      (node (ref "G5") (pin "3") (pinfunction "S_3") (pintype "passive"))
      (node (ref "RG2") (pin "1") (pinfunction "1_1") (pintype "passive"))
      (node (ref "RM14") (pin "2") (pinfunction "2_2") (pintype "passive"))
      (node (ref "RW10") (pin "1") (pinfunction "1_1") (pintype "passive"))
    )
    (net (code "37") (name "/GH3+") (class "Default")
      (node (ref "G6") (pin "3") (pinfunction "S_3") (pintype "passive"))
      (node (ref "RG3") (pin "1") (pinfunction "1_1") (pintype "passive"))
      (node (ref "RM21") (pin "2") (pinfunction "2_2") (pintype "passive"))
      (node (ref "RW12") (pin "1") (pinfunction "1_1") (pintype "passive"))
    )
    (net (code "38") (name "/G_H1") (class "Default")
      (node (ref "IR2101S-1") (pin "7") (pinfunction "HO_7") (pintype "output"))
      (node (ref "RW1") (pin "2") (pinfunction "2_2") (pintype "passive"))
    )
    (net (code "39") (name "/G_H2") (class "Default")
      (node (ref "IR2101S-2") (pin "7") (pinfunction "HO_7") (pintype "output"))
      (node (ref "RW3") (pin "2") (pinfunction "2_2") (pintype "passive"))
    )
    (net (code "40") (name "/G_H3") (class "Default")
      (node (ref "IR2101S-3") (pin "7") (pinfunction "HO_7") (pintype "output"))
      (node (ref "RW5") (pin "2") (pinfunction "2_2") (pintype "passive"))
    )
    (net (code "41") (name "/G_L1") (class "Default")
      (node (ref "IR2101S-1") (pin "5") (pinfunction "LO_5") (pintype "output"))
      (node (ref "RW7") (pin "2") (pinfunction "2_2") (pintype "passive"))
    )
    (net (code "42") (name "/G_L2") (class "Default")
      (node (ref "IR2101S-2") (pin "5") (pinfunction "LO_5") (pintype "output"))
      (node (ref "RW9") (pin "2") (pinfunction "2_2") (pintype "passive"))
    )
    (net (code "43") (name "/G_L3") (class "Default")
      (node (ref "IR2101S-3") (pin "5") (pinfunction "LO_5") (pintype "output"))
      (node (ref "RW11") (pin "2") (pinfunction "2_2") (pintype "passive"))
    )
    (net (code "44") (name "/HB1") (class "Default")
      (node (ref "CR3") (pin "2") (pinfunction "2_2") (pintype "passive"))
      (node (ref "G1") (pin "3") (pinfunction "S_3") (pintype "passive"))
      (node (ref "G4") (pin "2") (pinfunction "D_2") (pintype "passive"))
      (node (ref "H_bridge") (pin "3") (pinfunction "3_3") (pintype "passive"))
      (node (ref "IR2101S-1") (pin "6") (pinfunction "VS_6") (pintype "power_in"))
      (node (ref "RW2") (pin "1") (pinfunction "1_1") (pintype "passive"))
    )
    (net (code "45") (name "/HB2") (class "Default")
      (node (ref "CR6") (pin "2") (pinfunction "2_2") (pintype "passive"))
      (node (ref "G2") (pin "3") (pinfunction "S_3") (pintype "passive"))
      (node (ref "G5") (pin "2") (pinfunction "D_2") (pintype "passive"))
      (node (ref "H_bridge") (pin "2") (pinfunction "2_2") (pintype "passive"))
      (node (ref "IR2101S-2") (pin "6") (pinfunction "VS_6") (pintype "power_in"))
      (node (ref "RW4") (pin "1") (pinfunction "1_1") (pintype "passive"))
    )
    (net (code "46") (name "/HB3") (class "Default")
      (node (ref "CR9") (pin "2") (pinfunction "2_2") (pintype "passive"))
      (node (ref "G3") (pin "3") (pinfunction "S_3") (pintype "passive"))
      (node (ref "G6") (pin "2") (pinfunction "D_2") (pintype "passive"))
      (node (ref "H_bridge") (pin "1") (pinfunction "1_1") (pintype "passive"))
      (node (ref "IR2101S-3") (pin "6") (pinfunction "VS_6") (pintype "power_in"))
      (node (ref "RW6") (pin "1") (pinfunction "1_1") (pintype "passive"))
    )
    (net (code "47") (name "/P00_3") (class "Default")
      (node (ref "TC264D-1") (pin "14") (pinfunction "P00_3_14") (pintype "passive"))
    )
    (net (code "48") (name "/P00_7") (class "Default")
      (node (ref "TC264D-1") (pin "18") (pinfunction "P00_7_18") (pintype "passive"))
    )
    (net (code "49") (name "/P00_8") (class "Default")
      (node (ref "TC264D-1") (pin "19") (pinfunction "P00_8_19") (pintype "passive"))
    )
    (net (code "50") (name "/P00_9") (class "Default")
      (node (ref "TC264D-1") (pin "20") (pinfunction "P00_9_20") (pintype "passive"))
    )
    (net (code "51") (name "/P00_12") (class "Default")
      (node (ref "TC264D-1") (pin "21") (pinfunction "P00_12_21") (pintype "passive"))
    )
    (net (code "52") (name "/P02_0") (class "Default")
      (node (ref "IR2101S-1") (pin "2") (pinfunction "HIN_2") (pintype "input"))
      (node (ref "TC264D-1") (pin "1") (pinfunction "P02_0_1") (pintype "passive"))
    )
    (net (code "53") (name "/P02_1") (class "Default")
      (node (ref "IR2101S-1") (pin "3") (pinfunction "LIN_3") (pintype "input"))
      (node (ref "TC264D-1") (pin "2") (pinfunction "P02_1_2") (pintype "passive"))
    )
    (net (code "54") (name "/P02_6") (class "Default")
      (node (ref "TC264D-1") (pin "7") (pinfunction "P02_6_7") (pintype "passive"))
    )
    (net (code "55") (name "/P02_7") (class "Default")
      (node (ref "TC264D-1") (pin "8") (pinfunction "P02_7_8") (pintype "passive"))
    )
    (net (code "56") (name "/P02_8") (class "Default")
      (node (ref "TC264D-1") (pin "9") (pinfunction "P02_8_9") (pintype "passive"))
    )
    (net (code "57") (name "/P10_1") (class "Default")
      (node (ref "TC264D-1") (pin "140") (pinfunction "P10_1_140") (pintype "passive"))
    )
    (net (code "58") (name "/P10_2") (class "Default")
      (node (ref "TC264D-1") (pin "141") (pinfunction "P10_2_141") (pintype "passive"))
    )
    (net (code "59") (name "/P10_3") (class "Default")
      (node (ref "TC264D-1") (pin "142") (pinfunction "P10_3_142") (pintype "passive"))
    )
    (net (code "60") (name "/P10_5") (class "Default")
      (node (ref "TC264D-1") (pin "143") (pinfunction "P10_5_143") (pintype "passive"))
    )
    (net (code "61") (name "/P10_6") (class "Default")
      (node (ref "TC264D-1") (pin "144") (pinfunction "P10_6_144") (pintype "passive"))
    )
    (net (code "62") (name "/P11_2") (class "Default")
      (node (ref "TC264D-1") (pin "132") (pinfunction "P11_2_132") (pintype "passive"))
    )
    (net (code "63") (name "/P11_3") (class "Default")
      (node (ref "TC264D-1") (pin "133") (pinfunction "P11_3_133") (pintype "passive"))
    )
    (net (code "64") (name "/P11_6") (class "Default")
      (node (ref "TC264D-1") (pin "134") (pinfunction "P11_6_134") (pintype "passive"))
    )
    (net (code "65") (name "/P11_9") (class "Default")
      (node (ref "TC264D-1") (pin "135") (pinfunction "P11_9_135") (pintype "passive"))
    )
    (net (code "66") (name "/P11_10") (class "Default")
      (node (ref "TC264D-1") (pin "137") (pinfunction "P11_10_137") (pintype "passive"))
    )
    (net (code "67") (name "/P11_11") (class "Default")
      (node (ref "TC264D-1") (pin "138") (pinfunction "P11_11_138") (pintype "passive"))
    )
    (net (code "68") (name "/P11_12") (class "Default")
      (node (ref "TC264D-1") (pin "139") (pinfunction "P11_12_139") (pintype "passive"))
    )
    (net (code "69") (name "/P13_0") (class "Default")
      (node (ref "TC264D-1") (pin "128") (pinfunction "P13_0_128") (pintype "passive"))
    )
    (net (code "70") (name "/P13_1") (class "Default")
      (node (ref "TC264D-1") (pin "129") (pinfunction "P13_1_129") (pintype "passive"))
    )
    (net (code "71") (name "/P13_2") (class "Default")
      (node (ref "TC264D-1") (pin "130") (pinfunction "P13_2_130") (pintype "passive"))
    )
    (net (code "72") (name "/P13_3") (class "Default")
      (node (ref "TC264D-1") (pin "131") (pinfunction "P13_3_131") (pintype "passive"))
    )
    (net (code "73") (name "/P14_0") (class "Default")
      (node (ref "3232") (pin "11") (pinfunction "T1IN_11") (pintype "input"))
      (node (ref "TC264D-1") (pin "118") (pinfunction "P14_0_118") (pintype "passive"))
    )
    (net (code "74") (name "/P14_1") (class "Default")
      (node (ref "3232") (pin "12") (pinfunction "R1OUT_12") (pintype "output"))
      (node (ref "TC264D-1") (pin "119") (pinfunction "P14_1_119") (pintype "passive"))
    )
    (net (code "75") (name "/P14_2") (class "Default")
      (node (ref "TC264D-1") (pin "120") (pinfunction "P14_2_120") (pintype "passive"))
    )
    (net (code "76") (name "/P14_3") (class "Default")
      (node (ref "TC264D-1") (pin "121") (pinfunction "P14_3_121") (pintype "passive"))
    )
    (net (code "77") (name "/P14_4") (class "Default")
      (node (ref "TC264D-1") (pin "122") (pinfunction "P14_4_122") (pintype "passive"))
    )
    (net (code "78") (name "/P14_5") (class "Default")
      (node (ref "R12") (pin "6") (pinfunction "6_6") (pintype "passive"))
      (node (ref "TC264D-1") (pin "123") (pinfunction "P14_5_123") (pintype "passive"))
    )
    (net (code "79") (name "/P14_6") (class "Default")
      (node (ref "R12") (pin "5") (pinfunction "5_5") (pintype "passive"))
      (node (ref "TC264D-1") (pin "124") (pinfunction "P14_6_124") (pintype "passive"))
    )
    (net (code "80") (name "/P15_0") (class "Default")
      (node (ref "TC264D-1") (pin "109") (pinfunction "P15_0_109") (pintype "passive"))
    )
    (net (code "81") (name "/P15_1") (class "Default")
      (node (ref "TC264D-1") (pin "110") (pinfunction "P15_1_110") (pintype "passive"))
    )
    (net (code "82") (name "/P15_2") (class "Default")
      (node (ref "TC264D-1") (pin "111") (pinfunction "P15_2_111") (pintype "passive"))
    )
    (net (code "83") (name "/P15_3") (class "Default")
      (node (ref "TC264D-1") (pin "112") (pinfunction "P15_3_112") (pintype "passive"))
    )
    (net (code "84") (name "/P15_4") (class "Default")
      (node (ref "TC264D-1") (pin "113") (pinfunction "P15_4_113") (pintype "passive"))
    )
    (net (code "85") (name "/P15_5") (class "Default")
      (node (ref "TC264D-1") (pin "114") (pinfunction "P15_5_114") (pintype "passive"))
    )
    (net (code "86") (name "/P15_6") (class "Default")
      (node (ref "TC264D-1") (pin "115") (pinfunction "P15_6_115") (pintype "passive"))
    )
    (net (code "87") (name "/P15_7") (class "Default")
      (node (ref "TC264D-1") (pin "116") (pinfunction "P15_7_116") (pintype "passive"))
    )
    (net (code "88") (name "/P15_8") (class "Default")
      (node (ref "TC264D-1") (pin "117") (pinfunction "P15_8_117") (pintype "passive"))
    )
    (net (code "89") (name "/P20_3") (class "Default")
      (node (ref "TC264D-1") (pin "95") (pinfunction "P20_3_95") (pintype "passive"))
    )
    (net (code "90") (name "/P20_6") (class "Default")
      (node (ref "TC264D-1") (pin "100") (pinfunction "P20_6_100") (pintype "passive"))
    )
    (net (code "91") (name "/P20_7") (class "Default")
      (node (ref "TC264D-1") (pin "101") (pinfunction "P20_7_101") (pintype "passive"))
    )
    (net (code "92") (name "/P20_8") (class "Default")
      (node (ref "TC264D-1") (pin "102") (pinfunction "P20_8_102") (pintype "passive"))
    )
    (net (code "93") (name "/P20_9") (class "Default")
      (node (ref "TC264D-1") (pin "103") (pinfunction "P20_9_103") (pintype "passive"))
    )
    (net (code "94") (name "/P20_10") (class "Default")
      (node (ref "TC264D-1") (pin "104") (pinfunction "P20_10_104") (pintype "passive"))
    )
    (net (code "95") (name "/P20_11") (class "Default")
      (node (ref "TC264D-1") (pin "105") (pinfunction "P20_11_105") (pintype "passive"))
    )
    (net (code "96") (name "/P20_12") (class "Default")
      (node (ref "TC264D-1") (pin "106") (pinfunction "P20_12_106") (pintype "passive"))
    )
    (net (code "97") (name "/P20_13") (class "Default")
      (node (ref "TC264D-1") (pin "107") (pinfunction "P20_13_107") (pintype "passive"))
    )
    (net (code "98") (name "/P20_14") (class "Default")
      (node (ref "TC264D-1") (pin "108") (pinfunction "P20_14_108") (pintype "passive"))
    )
    (net (code "99") (name "/P21_2") (class "Default")
      (node (ref "TC264D-1") (pin "84") (pinfunction "P21_2_84") (pintype "passive"))
    )
    (net (code "100") (name "/P21_3") (class "Default")
      (node (ref "TC264D-1") (pin "85") (pinfunction "P21_3_85") (pintype "passive"))
    )
    (net (code "101") (name "/P21_4") (class "Default")
      (node (ref "TC264D-1") (pin "86") (pinfunction "P21_4_86") (pintype "passive"))
    )
    (net (code "102") (name "/P21_5") (class "Default")
      (node (ref "TC264D-1") (pin "87") (pinfunction "P21_5_87") (pintype "passive"))
    )
    (net (code "104") (name "/P22_0") (class "Default")
      (node (ref "TC264D-1") (pin "74") (pinfunction "P22_0_74") (pintype "passive"))
    )
    (net (code "105") (name "/P22_1") (class "Default")
      (node (ref "TC264D-1") (pin "75") (pinfunction "P22_1_75") (pintype "passive"))
    )
    (net (code "106") (name "/P22_2") (class "Default")
      (node (ref "TC264D-1") (pin "76") (pinfunction "P22_2_76") (pintype "passive"))
    )
    (net (code "107") (name "/P22_3") (class "Default")
      (node (ref "TC264D-1") (pin "77") (pinfunction "P22_3_77") (pintype "passive"))
    )
    (net (code "108") (name "/P23_1") (class "Default")
      (node (ref "TC264D-1") (pin "73") (pinfunction "P23_1_73") (pintype "passive"))
    )
    (net (code "109") (name "/P32_4") (class "Default")
      (node (ref "TC264D-1") (pin "72") (pinfunction "P32_4_72") (pintype "passive"))
    )
    (net (code "110") (name "/P33_4") (class "Default")
      (node (ref "TC264D-1") (pin "60") (pinfunction "P33_4_60") (pintype "passive"))
    )
    (net (code "111") (name "/P33_5") (class "Default")
      (node (ref "TC264D-1") (pin "61") (pinfunction "P33_5_61") (pintype "passive"))
    )
    (net (code "112") (name "/P33_6") (class "Default")
      (node (ref "TC264D-1") (pin "62") (pinfunction "P33_6_62") (pintype "passive"))
    )
    (net (code "113") (name "/P33_7") (class "Default")
      (node (ref "TC264D-1") (pin "63") (pinfunction "P33_7_63") (pintype "passive"))
    )
    (net (code "114") (name "/P33_8") (class "Default")
      (node (ref "TC264D-1") (pin "64") (pinfunction "P33_8_64") (pintype "passive"))
    )
    (net (code "115") (name "/P33_9") (class "Default")
      (node (ref "TC264D-1") (pin "65") (pinfunction "P33_9_65") (pintype "passive"))
    )
    (net (code "116") (name "/P33_10") (class "Default")
      (node (ref "TC264D-1") (pin "66") (pinfunction "P33_10_66") (pintype "passive"))
    )
    (net (code "117") (name "/P33_11") (class "Default")
      (node (ref "TC264D-1") (pin "67") (pinfunction "P33_11_67") (pintype "passive"))
    )
    (net (code "118") (name "/P33_12") (class "Default")
      (node (ref "TC264D-1") (pin "68") (pinfunction "P33_12_68") (pintype "passive"))
    )
    (net (code "119") (name "/P33_13") (class "Default")
      (node (ref "TC264D-1") (pin "69") (pinfunction "P33_13_69") (pintype "passive"))
    )
    (net (code "120") (name "/PAD01") (class "Default")
      (node (ref "CM5") (pin "2") (pinfunction "2_2") (pintype "passive"))
      (node (ref "RM9") (pin "1") (pinfunction "1_1") (pintype "passive"))
      (node (ref "TC264D-1") (pin "15") (pinfunction "P00_4_15") (pintype "passive"))
    )
    (net (code "121") (name "/PAD02") (class "Default")
      (node (ref "CM15") (pin "2") (pinfunction "2_2") (pintype "passive"))
      (node (ref "RM17") (pin "1") (pinfunction "1_1") (pintype "passive"))
      (node (ref "TC264D-1") (pin "16") (pinfunction "P00_5_16") (pintype "passive"))
    )
    (net (code "122") (name "/PAD03") (class "Default")
      (node (ref "CM16") (pin "2") (pinfunction "2_2") (pintype "passive"))
      (node (ref "RM24") (pin "1") (pinfunction "1_1") (pintype "passive"))
      (node (ref "TC264D-1") (pin "17") (pinfunction "P00_6_17") (pintype "passive"))
    )
    (net (code "123") (name "/PORST") (class "Default")
      (node (ref "DAP") (pin "10") (pinfunction "10_10") (pintype "passive"))
      (node (ref "R11") (pin "2") (pinfunction "2_2") (pintype "passive"))
      (node (ref "TC264D-1") (pin "97") (pinfunction "PORST#_97") (pintype "passive"))
    )
    (net (code "124") (name "/PT0") (class "Default")
      (node (ref "RD7") (pin "1") (pinfunction "1_1") (pintype "passive"))
      (node (ref "TC264D-1") (pin "11") (pinfunction "P00_0_11") (pintype "passive"))
    )
    (net (code "125") (name "/PT1") (class "Default")
      (node (ref "RD8") (pin "1") (pinfunction "1_1") (pintype "passive"))
      (node (ref "TC264D-1") (pin "12") (pinfunction "P00_1_12") (pintype "passive"))
    )
    (net (code "126") (name "/PT2") (class "Default")
      (node (ref "RD9") (pin "1") (pinfunction "1_1") (pintype "passive"))
    )
    (net (code "127") (name "/PT3") (class "Default")
      (node (ref "TC264D-1") (pin "13") (pinfunction "P00_2_13") (pintype "passive"))
    )
    (net (code "128") (name "/PWM2") (class "Default")
      (node (ref "IR2101S-2") (pin "2") (pinfunction "HIN_2") (pintype "input"))
    )
    (net (code "129") (name "/PWM3") (class "Default")
      (node (ref "IR2101S-2") (pin "3") (pinfunction "LIN_3") (pintype "input"))
      (node (ref "TC264D-1") (pin "3") (pinfunction "P02_2_3") (pintype "passive"))
    )
    (net (code "130") (name "/PWM4") (class "Default")
      (node (ref "IR2101S-3") (pin "2") (pinfunction "HIN_2") (pintype "input"))
      (node (ref "TC264D-1") (pin "4") (pinfunction "P02_3_4") (pintype "passive"))
    )
    (net (code "131") (name "/PWM5") (class "Default")
      (node (ref "IR2101S-3") (pin "3") (pinfunction "LIN_3") (pintype "input"))
      (node (ref "TC264D-1") (pin "5") (pinfunction "P02_4_5") (pintype "passive"))
    )
    (net (code "132") (name "/PWM6") (class "Default")
      (node (ref "TC264D-1") (pin "6") (pinfunction "P02_5_6") (pintype "passive"))
    )
    (net (code "133") (name "/P_SCI0_RX") (class "Default")
      (node (ref "3232") (pin "13") (pinfunction "R1IN_13") (pintype "input"))
      (node (ref "RS232") (pin "2") (pinfunction "2_2") (pintype "passive"))
    )
    (net (code "134") (name "/P_SCI0_TX") (class "Default")
      (node (ref "3232") (pin "14") (pinfunction "T1OUT_14") (pintype "output"))
      (node (ref "RS232") (pin "1") (pinfunction "1_1") (pintype "passive"))
    )
    (net (code "135") (name "/REF_2.5V") (class "Default")
      (node (ref "CM6") (pin "1") (pinfunction "1_1") (pintype "passive"))
      (node (ref "MCP602-1") (pin "6") (pinfunction "-IN_B_6") (pintype "power_in"))
      (node (ref "MCP602-1") (pin "7") (pinfunction "OUT_B_7") (pintype "power_in"))
      (node (ref "RM16") (pin "1") (pinfunction "1_1") (pintype "passive"))
      (node (ref "RM23") (pin "2") (pinfunction "2_2") (pintype "passive"))
      (node (ref "RM8") (pin "1") (pinfunction "1_1") (pintype "passive"))
    )
    (net (code "136") (name "/TCK") (class "Default")
      (node (ref "DAP") (pin "4") (pinfunction "4_4") (pintype "passive"))
      (node (ref "TC264D-1") (pin "92") (pinfunction "TCK_92") (pintype "passive"))
    )
    (net (code "137") (name "/TDO") (class "Default")
      (node (ref "DAP") (pin "6") (pinfunction "6_6") (pintype "passive"))
      (node (ref "TC264D-1") (pin "90") (pinfunction "P21_7/TDO_90") (pintype "passive"))
    )
    (net (code "138") (name "/TMS") (class "Default")
      (node (ref "DAP") (pin "2") (pinfunction "2_2") (pintype "passive"))
      (node (ref "TC264D-1") (pin "89") (pinfunction "TMS_89") (pintype "passive"))
    )
    (net (code "139") (name "/TRST") (class "Default")
      (node (ref "DAP") (pin "8") (pinfunction "8_8") (pintype "passive"))
      (node (ref "R11") (pin "4") (pinfunction "4_4") (pintype "passive"))
      (node (ref "TC264D-1") (pin "91") (pinfunction "TRST#_91") (pintype "passive"))
    )
    (net (code "140") (name "/VCC 24V") (class "Default")
      (node (ref "C51") (pin "2") (pinfunction "2_2") (pintype "passive"))
      (node (ref "C52") (pin "2") (pinfunction "2_2") (pintype "passive"))
      (node (ref "CV0") (pin "1") (pinfunction "1_1") (pintype "passive"))
      (node (ref "DV00") (pin "2") (pinfunction "K_2") (pintype "passive"))
      (node (ref "LMR36520") (pin "2") (pinfunction "VIN_2") (pintype "passive"))
      (node (ref "LMR36520") (pin "3") (pinfunction "EN_3") (pintype "passive"))
    )
    (net (code "141") (name "/VGATE1N") (class "Default")
      (node (ref "BSL215C") (pin "1") (pinfunction "G1_1") (pintype "passive"))
      (node (ref "TC264D-1") (pin "70") (pinfunction "P32_0/VGATE1N_70") (pintype "passive"))
    )
    (net (code "142") (name "/VGATE1P") (class "Default")
      (node (ref "BSL215C") (pin "3") (pinfunction "G2_3") (pintype "passive"))
      (node (ref "TC264D-1") (pin "71") (pinfunction "VGATE1P_71") (pintype "passive"))
    )
    (net (code "143") (name "GND") (class "Default")
      (node (ref "3232") (pin "15") (pinfunction "GND_15") (pintype "power_in"))
      (node (ref "AZ1117CR2-3.3") (pin "1") (pinfunction "ADJ/GND_1") (pintype "passive"))
      (node (ref "BSL215C") (pin "5") (pinfunction "S1_5") (pintype "passive"))
      (node (ref "C1") (pin "2") (pinfunction "2_2") (pintype "passive"))
      (node (ref "C10") (pin "2") (pinfunction "2_2") (pintype "passive"))
      (node (ref "C11") (pin "1") (pinfunction "1_1") (pintype "passive"))
      (node (ref "C12") (pin "1") (pinfunction "1_1") (pintype "passive"))
      (node (ref "C13") (pin "2") (pinfunction "2_2") (pintype "passive"))
      (node (ref "C15") (pin "1") (pinfunction "1_1") (pintype "passive"))
      (node (ref "C16") (pin "1") (pinfunction "1_1") (pintype "passive"))
      (node (ref "C17") (pin "2") (pinfunction "2_2") (pintype "passive"))
      (node (ref "C18") (pin "2") (pinfunction "2_2") (pintype "passive"))
      (node (ref "C19") (pin "1") (pinfunction "1_1") (pintype "passive"))
      (node (ref "C2") (pin "1") (pinfunction "1_1") (pintype "passive"))
      (node (ref "C20") (pin "1") (pinfunction "1_1") (pintype "passive"))
      (node (ref "C21") (pin "2") (pinfunction "2_2") (pintype "passive"))
      (node (ref "C22") (pin "2") (pinfunction "2_2") (pintype "passive"))
      (node (ref "C3") (pin "1") (pinfunction "1_1") (pintype "passive"))
      (node (ref "C4") (pin "1") (pinfunction "1_1") (pintype "passive"))
      (node (ref "C5") (pin "1") (pinfunction "1_1") (pintype "passive"))
      (node (ref "C51") (pin "1") (pinfunction "1_1") (pintype "passive"))
      (node (ref "C52") (pin "1") (pinfunction "1_1") (pintype "passive"))
      (node (ref "C54") (pin "1") (pinfunction "1_1") (pintype "passive"))
      (node (ref "C55") (pin "2") (pinfunction "2_2") (pintype "passive"))
      (node (ref "C56") (pin "2") (pinfunction "2_2") (pintype "passive"))
      (node (ref "C6") (pin "2") (pinfunction "2_2") (pintype "passive"))
      (node (ref "C7") (pin "2") (pinfunction "2_2") (pintype "passive"))
      (node (ref "C8") (pin "2") (pinfunction "2_2") (pintype "passive"))
      (node (ref "C9") (pin "2") (pinfunction "2_2") (pintype "passive"))
      (node (ref "CD1") (pin "2") (pinfunction "2_2") (pintype "passive"))
      (node (ref "CD2") (pin "2") (pinfunction "2_2") (pintype "passive"))
      (node (ref "CD3") (pin "2") (pinfunction "2_2") (pintype "passive"))
      (node (ref "CD4") (pin "2") (pinfunction "2_2") (pintype "passive"))
      (node (ref "CD5") (pin "2") (pinfunction "2_2") (pintype "passive"))
      (node (ref "CM1") (pin "1") (pinfunction "1_1") (pintype "passive"))
      (node (ref "CM11") (pin "1") (pinfunction "1_1") (pintype "passive"))
      (node (ref "CM12") (pin "1") (pinfunction "1_1") (pintype "passive"))
      (node (ref "CM15") (pin "1") (pinfunction "1_1") (pintype "passive"))
      (node (ref "CM16") (pin "1") (pinfunction "1_1") (pintype "passive"))
      (node (ref "CM2") (pin "1") (pinfunction "1_1") (pintype "passive"))
      (node (ref "CM3") (pin "1") (pinfunction "1_1") (pintype "passive"))
      (node (ref "CM5") (pin "1") (pinfunction "1_1") (pintype "passive"))
      (node (ref "CM6") (pin "2") (pinfunction "2_2") (pintype "passive"))
      (node (ref "CR1") (pin "2") (pinfunction "2_2") (pintype "passive"))
      (node (ref "CR2") (pin "2") (pinfunction "2_2") (pintype "passive"))
      (node (ref "CR4") (pin "2") (pinfunction "2_2") (pintype "passive"))
      (node (ref "CR5") (pin "2") (pinfunction "2_2") (pintype "passive"))
      (node (ref "CR7") (pin "2") (pinfunction "2_2") (pintype "passive"))
      (node (ref "CR8") (pin "2") (pinfunction "2_2") (pintype "passive"))
      (node (ref "CV0") (pin "2") (pinfunction "2_2") (pintype "passive"))
      (node (ref "CW1") (pin "1") (pinfunction "1_1") (pintype "passive"))
      (node (ref "CW10") (pin "1") (pinfunction "1_1") (pintype "passive"))
      (node (ref "CW11") (pin "1") (pinfunction "1_1") (pintype "passive"))
      (node (ref "CW12") (pin "1") (pinfunction "1_1") (pintype "passive"))
      (node (ref "CW2") (pin "1") (pinfunction "1_1") (pintype "passive"))
      (node (ref "CW3") (pin "2") (pinfunction "2_2") (pintype "passive"))
      (node (ref "CW4") (pin "1") (pinfunction "1_1") (pintype "passive"))
      (node (ref "CW5") (pin "1") (pinfunction "1_1") (pintype "passive"))
      (node (ref "CW6") (pin "1") (pinfunction "1_1") (pintype "passive"))
      (node (ref "DAP") (pin "3") (pinfunction "3_3") (pintype "passive"))
      (node (ref "DAP") (pin "5") (pinfunction "5_5") (pintype "passive"))
      (node (ref "DAP") (pin "7") (pinfunction "7_7") (pintype "passive"))
      (node (ref "DAP") (pin "9") (pinfunction "9_9") (pintype "passive"))
      (node (ref "HALL_PWR") (pin "1") (pinfunction "1_1") (pintype "passive"))
      (node (ref "IR2101S-1") (pin "4") (pinfunction "COM_4") (pintype "power_in"))
      (node (ref "IR2101S-2") (pin "4") (pinfunction "COM_4") (pintype "power_in"))
      (node (ref "IR2101S-3") (pin "4") (pinfunction "COM_4") (pintype "power_in"))
      (node (ref "LB3") (pin "2") (pinfunction "2_2") (pintype "passive"))
      (node (ref "LM2940-5V") (pin "4") (pinfunction "GND_4") (pintype "power_in"))
      (node (ref "LMR36520") (pin "1") (pinfunction "PGND_1") (pintype "passive"))
      (node (ref "LMR36520") (pin "9") (pinfunction "EP_9") (pintype "passive"))
      (node (ref "MCP602-1") (pin "4") (pinfunction "-VS_4") (pintype "power_in"))
      (node (ref "MCP602-2") (pin "4") (pinfunction "-VS_4") (pintype "power_in"))
      (node (ref "POWER_24V") (pin "1") (pinfunction "1_1") (pintype "passive"))
      (node (ref "R12") (pin "3") (pinfunction "3_3") (pintype "passive"))
      (node (ref "R12") (pin "4") (pinfunction "4_4") (pintype "passive"))
      (node (ref "R51") (pin "2") (pinfunction "2_2") (pintype "passive"))
      (node (ref "RG1") (pin "2") (pinfunction "2_2") (pintype "passive"))
      (node (ref "RG2") (pin "2") (pinfunction "2_2") (pintype "passive"))
      (node (ref "RG3") (pin "2") (pinfunction "2_2") (pintype "passive"))
      (node (ref "RM11") (pin "2") (pinfunction "2_2") (pintype "passive"))
      (node (ref "RM18") (pin "2") (pinfunction "2_2") (pintype "passive"))
      (node (ref "RM3") (pin "2") (pinfunction "2_2") (pintype "passive"))
      (node (ref "RS232") (pin "3") (pinfunction "3_3") (pintype "passive"))
      (node (ref "TC264D-1") (pin "145") (pinfunction "EP_145") (pintype "passive"))
      (node (ref "TC264D-1") (pin "80") (pinfunction "VSS_80") (pintype "passive"))
      (node (ref "TX_C_4") (pin "1") (pinfunction "1_1") (pintype "passive"))
      (node (ref "TX_C_5") (pin "1") (pinfunction "1_1") (pintype "passive"))
      (node (ref "Y1") (pin "2") (pinfunction "GND_2") (pintype "power_in"))
      (node (ref "Y1") (pin "4") (pinfunction "GND_4") (pintype "power_in"))
    )
    (net (code "144") (name "Net-(3232-C1+)") (class "Default")
      (node (ref "3232") (pin "1") (pinfunction "C1+_1") (pintype "passive"))
      (node (ref "TX_C_2") (pin "2") (pinfunction "2_2") (pintype "passive"))
    )
    (net (code "145") (name "Net-(3232-C1-)") (class "Default")
      (node (ref "3232") (pin "3") (pinfunction "C1-_3") (pintype "passive"))
      (node (ref "TX_C_2") (pin "1") (pinfunction "1_1") (pintype "passive"))
    )
    (net (code "146") (name "Net-(3232-C2+)") (class "Default")
      (node (ref "3232") (pin "4") (pinfunction "C2+_4") (pintype "passive"))
      (node (ref "TX_C_3") (pin "2") (pinfunction "2_2") (pintype "passive"))
    )
    (net (code "147") (name "Net-(3232-C2-)") (class "Default")
      (node (ref "3232") (pin "5") (pinfunction "C2-_5") (pintype "passive"))
      (node (ref "TX_C_3") (pin "1") (pinfunction "1_1") (pintype "passive"))
    )
    (net (code "148") (name "Net-(3232-V+)") (class "Default")
      (node (ref "3232") (pin "2") (pinfunction "V+_2") (pintype "power_in"))
      (node (ref "TX_C_1") (pin "1") (pinfunction "1_1") (pintype "passive"))
    )
    (net (code "149") (name "Net-(3232-V-)") (class "Default")
      (node (ref "3232") (pin "6") (pinfunction "V-_6") (pintype "power_in"))
      (node (ref "TX_C_4") (pin "2") (pinfunction "2_2") (pintype "passive"))
    )
    (net (code "150") (name "Net-(BSL215C-D1)") (class "Default")
      (node (ref "BSL215C") (pin "4") (pinfunction "D2_4") (pintype "passive"))
      (node (ref "BSL215C") (pin "6") (pinfunction "D1_6") (pintype "passive"))
      (node (ref "L11") (pin "1") (pinfunction "1_1") (pintype "passive"))
    )
    (net (code "151") (name "Net-(C12-Pad2)") (class "Default")
      (node (ref "C12") (pin "2") (pinfunction "2_2") (pintype "passive"))
      (node (ref "TC264D-1") (pin "125") (pinfunction "VEXT_125") (pintype "passive"))
    )
    (net (code "152") (name "Net-(CD1-Pad1)") (class "Default")
      (node (ref "CD1") (pin "1") (pinfunction "1_1") (pintype "passive"))
      (node (ref "RD1") (pin "2") (pinfunction "2_2") (pintype "passive"))
      (node (ref "RD4") (pin "1") (pinfunction "1_1") (pintype "passive"))
      (node (ref "RD7") (pin "2") (pinfunction "2_2") (pintype "passive"))
    )
    (net (code "153") (name "Net-(CD2-Pad1)") (class "Default")
      (node (ref "CD2") (pin "1") (pinfunction "1_1") (pintype "passive"))
      (node (ref "RD2") (pin "2") (pinfunction "2_2") (pintype "passive"))
      (node (ref "RD5") (pin "1") (pinfunction "1_1") (pintype "passive"))
      (node (ref "RD8") (pin "2") (pinfunction "2_2") (pintype "passive"))
    )
    (net (code "154") (name "Net-(CD3-Pad1)") (class "Default")
      (node (ref "CD3") (pin "1") (pinfunction "1_1") (pintype "passive"))
      (node (ref "RD3") (pin "2") (pinfunction "2_2") (pintype "passive"))
      (node (ref "RD6") (pin "1") (pinfunction "1_1") (pintype "passive"))
      (node (ref "RD9") (pin "2") (pinfunction "2_2") (pintype "passive"))
    )
    (net (code "155") (name "Net-(CM4-Pad1)") (class "Default")
      (node (ref "CM4") (pin "1") (pinfunction "1_1") (pintype "passive"))
      (node (ref "RM6") (pin "1") (pinfunction "1_1") (pintype "passive"))
      (node (ref "RM7") (pin "2") (pinfunction "2_2") (pintype "passive"))
    )
    (net (code "156") (name "Net-(CM4-Pad2)") (class "Default")
      (node (ref "CM4") (pin "2") (pinfunction "2_2") (pintype "passive"))
      (node (ref "RM3") (pin "1") (pinfunction "1_1") (pintype "passive"))
      (node (ref "RM4") (pin "2") (pinfunction "2_2") (pintype "passive"))
    )
    (net (code "157") (name "Net-(CM13-Pad1)") (class "Default")
      (node (ref "CM13") (pin "1") (pinfunction "1_1") (pintype "passive"))
      (node (ref "RM18") (pin "1") (pinfunction "1_1") (pintype "passive"))
      (node (ref "RM19") (pin "2") (pinfunction "2_2") (pintype "passive"))
    )
    (net (code "158") (name "Net-(CM13-Pad2)") (class "Default")
      (node (ref "CM13") (pin "2") (pinfunction "2_2") (pintype "passive"))
      (node (ref "RM21") (pin "1") (pinfunction "1_1") (pintype "passive"))
      (node (ref "RM22") (pin "2") (pinfunction "2_2") (pintype "passive"))
    )
    (net (code "159") (name "Net-(CM14-Pad1)") (class "Default")
      (node (ref "CM14") (pin "1") (pinfunction "1_1") (pintype "passive"))
      (node (ref "RM14") (pin "1") (pinfunction "1_1") (pintype "passive"))
      (node (ref "RM15") (pin "2") (pinfunction "2_2") (pintype "passive"))
    )
    (net (code "160") (name "Net-(CM14-Pad2)") (class "Default")
      (node (ref "CM14") (pin "2") (pinfunction "2_2") (pintype "passive"))
      (node (ref "RM11") (pin "1") (pinfunction "1_1") (pintype "passive"))
      (node (ref "RM12") (pin "2") (pinfunction "2_2") (pintype "passive"))
    )
    (net (code "161") (name "Net-(DR1-K)") (class "Default")
      (node (ref "CR3") (pin "1") (pinfunction "1_1") (pintype "passive"))
      (node (ref "DR1") (pin "2") (pinfunction "K_2") (pintype "passive"))
      (node (ref "IR2101S-1") (pin "8") (pinfunction "VB_8") (pintype "power_in"))
    )
    (net (code "162") (name "Net-(DR2-K)") (class "Default")
      (node (ref "CR6") (pin "1") (pinfunction "1_1") (pintype "passive"))
      (node (ref "DR2") (pin "2") (pinfunction "K_2") (pintype "passive"))
      (node (ref "IR2101S-2") (pin "8") (pinfunction "VB_8") (pintype "power_in"))
    )
    (net (code "163") (name "Net-(DR3-K)") (class "Default")
      (node (ref "CR9") (pin "1") (pinfunction "1_1") (pintype "passive"))
      (node (ref "DR3") (pin "2") (pinfunction "K_2") (pintype "passive"))
      (node (ref "IR2101S-3") (pin "8") (pinfunction "VB_8") (pintype "power_in"))
    )
    (net (code "164") (name "Net-(G1-G)") (class "Default")
      (node (ref "G1") (pin "1") (pinfunction "G_1") (pintype "passive"))
      (node (ref "RW1") (pin "1") (pinfunction "1_1") (pintype "passive"))
      (node (ref "RW2") (pin "2") (pinfunction "2_2") (pintype "passive"))
    )
    (net (code "165") (name "Net-(G2-G)") (class "Default")
      (node (ref "G2") (pin "1") (pinfunction "G_1") (pintype "passive"))
      (node (ref "RW3") (pin "1") (pinfunction "1_1") (pintype "passive"))
      (node (ref "RW4") (pin "2") (pinfunction "2_2") (pintype "passive"))
    )
    (net (code "166") (name "Net-(G3-G)") (class "Default")
      (node (ref "G3") (pin "1") (pinfunction "G_1") (pintype "passive"))
      (node (ref "RW5") (pin "1") (pinfunction "1_1") (pintype "passive"))
      (node (ref "RW6") (pin "2") (pinfunction "2_2") (pintype "passive"))
    )
    (net (code "167") (name "Net-(G4-G)") (class "Default")
      (node (ref "G4") (pin "1") (pinfunction "G_1") (pintype "passive"))
      (node (ref "RW7") (pin "1") (pinfunction "1_1") (pintype "passive"))
      (node (ref "RW8") (pin "2") (pinfunction "2_2") (pintype "passive"))
    )
    (net (code "168") (name "Net-(G5-G)") (class "Default")
      (node (ref "G5") (pin "1") (pinfunction "G_1") (pintype "passive"))
      (node (ref "RW10") (pin "2") (pinfunction "2_2") (pintype "passive"))
      (node (ref "RW9") (pin "1") (pinfunction "1_1") (pintype "passive"))
    )
    (net (code "169") (name "Net-(G6-G)") (class "Default")
      (node (ref "G6") (pin "1") (pinfunction "G_1") (pintype "passive"))
      (node (ref "RW11") (pin "1") (pinfunction "1_1") (pintype "passive"))
      (node (ref "RW12") (pin "2") (pinfunction "2_2") (pintype "passive"))
    )
    (net (code "170") (name "Net-(HALL_signal-Pad1)") (class "Default")
      (node (ref "HALL_signal") (pin "1") (pinfunction "1_1") (pintype "passive"))
      (node (ref "RD6") (pin "2") (pinfunction "2_2") (pintype "passive"))
    )
    (net (code "171") (name "Net-(HALL_signal-Pad2)") (class "Default")
      (node (ref "HALL_signal") (pin "2") (pinfunction "2_2") (pintype "passive"))
      (node (ref "RD5") (pin "2") (pinfunction "2_2") (pintype "passive"))
    )
    (net (code "172") (name "Net-(HALL_signal-Pad3)") (class "Default")
      (node (ref "HALL_signal") (pin "3") (pinfunction "3_3") (pintype "passive"))
      (node (ref "RD4") (pin "2") (pinfunction "2_2") (pintype "passive"))
    )
    (net (code "173") (name "Net-(LMR36520-BOOT)") (class "Default")
      (node (ref "C53") (pin "2") (pinfunction "2_2") (pintype "passive"))
      (node (ref "LMR36520") (pin "7") (pinfunction "BOOT_7") (pintype "passive"))
    )
    (net (code "174") (name "Net-(LMR36520-FB)") (class "Default")
      (node (ref "LMR36520") (pin "5") (pinfunction "FB_5") (pintype "passive"))
      (node (ref "R51") (pin "1") (pinfunction "1_1") (pintype "passive"))
      (node (ref "R52") (pin "2") (pinfunction "2_2") (pintype "passive"))
    )
    (net (code "175") (name "Net-(LMR36520-SW)") (class "Default")
      (node (ref "C53") (pin "1") (pinfunction "1_1") (pintype "passive"))
      (node (ref "LMR36520") (pin "8") (pinfunction "SW_8") (pintype "passive"))
      (node (ref "LV1") (pin "1") (pinfunction "1_1") (pintype "passive"))
    )
    (net (code "176") (name "Net-(LMR36520-VCC)") (class "Default")
      (node (ref "C54") (pin "2") (pinfunction "2_2") (pintype "passive"))
      (node (ref "LMR36520") (pin "6") (pinfunction "VCC_6") (pintype "passive"))
    )
    (net (code "177") (name "Net-(MCP602-1-+IN_A)") (class "Default")
      (node (ref "MCP602-1") (pin "3") (pinfunction "+IN_A_3") (pintype "power_in"))
      (node (ref "RM7") (pin "1") (pinfunction "1_1") (pintype "passive"))
      (node (ref "RM8") (pin "2") (pinfunction "2_2") (pintype "passive"))
    )
    (net (code "178") (name "Net-(MCP602-1-+IN_B)") (class "Default")
      (node (ref "CM3") (pin "2") (pinfunction "2_2") (pintype "passive"))
      (node (ref "MCP602-1") (pin "5") (pinfunction "+IN_B_5") (pintype "power_in"))
      (node (ref "RM1") (pin "1") (pinfunction "1_1") (pintype "passive"))
      (node (ref "RM2") (pin "2") (pinfunction "2_2") (pintype "passive"))
    )
    (net (code "179") (name "Net-(MCP602-1--IN_A)") (class "Default")
      (node (ref "MCP602-1") (pin "2") (pinfunction "-IN_A_2") (pintype "power_in"))
      (node (ref "RM4") (pin "1") (pinfunction "1_1") (pintype "passive"))
      (node (ref "RM5") (pin "2") (pinfunction "2_2") (pintype "passive"))
    )
    (net (code "180") (name "Net-(MCP602-1-OUT_A)") (class "Default")
      (node (ref "MCP602-1") (pin "1") (pinfunction "OUT_A_1") (pintype "power_in"))
      (node (ref "RM5") (pin "1") (pinfunction "1_1") (pintype "passive"))
      (node (ref "RM9") (pin "2") (pinfunction "2_2") (pintype "passive"))
    )
    (net (code "181") (name "Net-(MCP602-1-VCC)") (class "Default")
      (node (ref "CM1") (pin "2") (pinfunction "2_2") (pintype "passive"))
      (node (ref "CM2") (pin "2") (pinfunction "2_2") (pintype "passive"))
      (node (ref "LM1") (pin "2") (pinfunction "2_2") (pintype "passive"))
      (node (ref "MCP602-1") (pin "8") (pinfunction "VCC_8") (pintype "power_in"))
      (node (ref "RM1") (pin "2") (pinfunction "2_2") (pintype "passive"))
    )
    (net (code "182") (name "Net-(MCP602-2-+IN_A)") (class "Default")
      (node (ref "MCP602-2") (pin "3") (pinfunction "+IN_A_3") (pintype "power_in"))
      (node (ref "RM15") (pin "1") (pinfunction "1_1") (pintype "passive"))
      (node (ref "RM16") (pin "2") (pinfunction "2_2") (pintype "passive"))
    )
    (net (code "183") (name "Net-(MCP602-2-+IN_B)") (class "Default")
      (node (ref "MCP602-2") (pin "5") (pinfunction "+IN_B_5") (pintype "power_in"))
      (node (ref "RM22") (pin "1") (pinfunction "1_1") (pintype "passive"))
      (node (ref "RM23") (pin "1") (pinfunction "1_1") (pintype "passive"))
    )
    (net (code "184") (name "Net-(MCP602-2--IN_A)") (class "Default")
      (node (ref "MCP602-2") (pin "2") (pinfunction "-IN_A_2") (pintype "power_in"))
      (node (ref "RM12") (pin "1") (pinfunction "1_1") (pintype "passive"))
      (node (ref "RM13") (pin "2") (pinfunction "2_2") (pintype "passive"))
    )
    (net (code "185") (name "Net-(MCP602-2--IN_B)") (class "Default")
      (node (ref "MCP602-2") (pin "6") (pinfunction "-IN_B_6") (pintype "power_in"))
      (node (ref "RM19") (pin "1") (pinfunction "1_1") (pintype "passive"))
      (node (ref "RM20") (pin "1") (pinfunction "1_1") (pintype "passive"))
    )
    (net (code "186") (name "Net-(MCP602-2-OUT_A)") (class "Default")
      (node (ref "MCP602-2") (pin "1") (pinfunction "OUT_A_1") (pintype "power_in"))
      (node (ref "RM13") (pin "1") (pinfunction "1_1") (pintype "passive"))
      (node (ref "RM17") (pin "2") (pinfunction "2_2") (pintype "passive"))
    )
    (net (code "187") (name "Net-(MCP602-2-OUT_B)") (class "Default")
      (node (ref "MCP602-2") (pin "7") (pinfunction "OUT_B_7") (pintype "power_in"))
      (node (ref "RM20") (pin "2") (pinfunction "2_2") (pintype "passive"))
      (node (ref "RM24") (pin "2") (pinfunction "2_2") (pintype "passive"))
    )
    (net (code "188") (name "Net-(MCP602-2-VCC)") (class "Default")
      (node (ref "CM11") (pin "2") (pinfunction "2_2") (pintype "passive"))
      (node (ref "CM12") (pin "2") (pinfunction "2_2") (pintype "passive"))
      (node (ref "LM2") (pin "2") (pinfunction "2_2") (pintype "passive"))
      (node (ref "MCP602-2") (pin "8") (pinfunction "VCC_8") (pintype "power_in"))
    )
    (net (code "189") (name "Net-(TC264D-1-P20_2{slash}TESTMODE#)") (class "Default")
      (node (ref "R11") (pin "3") (pinfunction "3_3") (pintype "passive"))
      (node (ref "TC264D-1") (pin "94") (pinfunction "P20_2/TESTMODE#_94") (pintype "passive"))
    )
    (net (code "190") (name "Net-(TC264D-1-XTAL1)") (class "Default")
      (node (ref "C15") (pin "2") (pinfunction "2_2") (pintype "passive"))
      (node (ref "R1") (pin "1") (pinfunction "1_1") (pintype "passive"))
      (node (ref "TC264D-1") (pin "81") (pinfunction "XTAL1_81") (pintype "passive"))
      (node (ref "Y1") (pin "1") (pinfunction "Y1_1") (pintype "power_in"))
    )
    (net (code "191") (name "Net-(TC264D-1-XTAL2)") (class "Default")
      (node (ref "C16") (pin "2") (pinfunction "2_2") (pintype "passive"))
      (node (ref "R1") (pin "2") (pinfunction "2_2") (pintype "passive"))
      (node (ref "TC264D-1") (pin "82") (pinfunction "XTAL2_82") (pintype "passive"))
      (node (ref "Y1") (pin "3") (pinfunction "Y2_3") (pintype "power_in"))
    )
    (net (code "192") (name "VC 1V3") (class "Default")
      (node (ref "C1") (pin "1") (pinfunction "1_1") (pintype "passive"))
      (node (ref "C2") (pin "2") (pinfunction "2_2") (pintype "passive"))
      (node (ref "C3") (pin "2") (pinfunction "2_2") (pintype "passive"))
      (node (ref "C4") (pin "2") (pinfunction "2_2") (pintype "passive"))
      (node (ref "C8") (pin "1") (pinfunction "1_1") (pintype "passive"))
      (node (ref "CW6") (pin "2") (pinfunction "2_2") (pintype "passive"))
      (node (ref "L11") (pin "2") (pinfunction "2_2") (pintype "passive"))
      (node (ref "TC264D-1") (pin "10") (pinfunction "VDD/VDDSB_10") (pintype "passive"))
      (node (ref "TC264D-1") (pin "22") (pinfunction "VDD_22") (pintype "passive"))
      (node (ref "TC264D-1") (pin "58") (pinfunction "VDD_58") (pintype "passive"))
      (node (ref "TC264D-1") (pin "79") (pinfunction "VDD_79") (pintype "passive"))
      (node (ref "TC264D-1") (pin "99") (pinfunction "VDD_99") (pintype "passive"))
    )
    (net (code "193") (name "VC 3V3") (class "Default")
      (node (ref "AZ1117CR2-3.3") (pin "3") (pinfunction "OUTPUT_3") (pintype "passive"))
      (node (ref "BSL215C") (pin "2") (pinfunction "S2_2") (pintype "passive"))
      (node (ref "C5") (pin "2") (pinfunction "2_2") (pintype "passive"))
      (node (ref "C6") (pin "1") (pinfunction "1_1") (pintype "passive"))
      (node (ref "C7") (pin "1") (pinfunction "1_1") (pintype "passive"))
      (node (ref "CW11") (pin "2") (pinfunction "2_2") (pintype "passive"))
      (node (ref "CW12") (pin "2") (pinfunction "2_2") (pintype "passive"))
      (node (ref "CW5") (pin "2") (pinfunction "2_2") (pintype "passive"))
      (node (ref "TC264D-1") (pin "126") (pinfunction "VDDP3_126") (pintype "passive"))
      (node (ref "TC264D-1") (pin "127") (pinfunction "VDDFL3_127") (pintype "passive"))
      (node (ref "TC264D-1") (pin "83") (pinfunction "VDDP3_83") (pintype "passive"))
    )
    (net (code "194") (name "VC 5V") (class "Default")
      (node (ref "3232") (pin "16") (pinfunction "VCC_16") (pintype "power_in"))
      (node (ref "AZ1117CR2-3.3") (pin "2") (pinfunction "INPUT_2") (pintype "passive"))
      (node (ref "C10") (pin "1") (pinfunction "1_1") (pintype "passive"))
      (node (ref "C11") (pin "2") (pinfunction "2_2") (pintype "passive"))
      (node (ref "C13") (pin "1") (pinfunction "1_1") (pintype "passive"))
      (node (ref "C21") (pin "1") (pinfunction "1_1") (pintype "passive"))
      (node (ref "C22") (pin "1") (pinfunction "1_1") (pintype "passive"))
      (node (ref "C9") (pin "1") (pinfunction "1_1") (pintype "passive"))
      (node (ref "CD4") (pin "1") (pinfunction "1_1") (pintype "passive"))
      (node (ref "CD5") (pin "1") (pinfunction "1_1") (pintype "passive"))
      (node (ref "CW10") (pin "2") (pinfunction "2_2") (pintype "passive"))
      (node (ref "CW3") (pin "1") (pinfunction "1_1") (pintype "passive"))
      (node (ref "CW4") (pin "2") (pinfunction "2_2") (pintype "passive"))
      (node (ref "DAP") (pin "1") (pinfunction "1_1") (pintype "passive"))
      (node (ref "HALL_PWR") (pin "2") (pinfunction "2_2") (pintype "passive"))
      (node (ref "LB2") (pin "2") (pinfunction "2_2") (pintype "passive"))
      (node (ref "LM1") (pin "1") (pinfunction "1_1") (pintype "passive"))
      (node (ref "LM2") (pin "1") (pinfunction "1_1") (pintype "passive"))
      (node (ref "LM2940-5V") (pin "3") (pinfunction "OUT_3") (pintype "power_in"))
      (node (ref "R11") (pin "5") (pinfunction "5_5") (pintype "passive"))
      (node (ref "R11") (pin "6") (pinfunction "6_6") (pintype "passive"))
      (node (ref "R11") (pin "7") (pinfunction "7_7") (pintype "passive"))
      (node (ref "RD1") (pin "1") (pinfunction "1_1") (pintype "passive"))
      (node (ref "RD2") (pin "1") (pinfunction "1_1") (pintype "passive"))
      (node (ref "RD3") (pin "1") (pinfunction "1_1") (pintype "passive"))
      (node (ref "TC264D-1") (pin "136") (pinfunction "VFLEX_136") (pintype "passive"))
      (node (ref "TC264D-1") (pin "23") (pinfunction "VEXT_23") (pintype "passive"))
      (node (ref "TC264D-1") (pin "59") (pinfunction "VEXT_59") (pintype "passive"))
      (node (ref "TC264D-1") (pin "78") (pinfunction "VEXT_78") (pintype "passive"))
      (node (ref "TX_C_1") (pin "2") (pinfunction "2_2") (pintype "passive"))
      (node (ref "TX_C_5") (pin "2") (pinfunction "2_2") (pintype "passive"))
    )
    (net (code "195") (name "VC 7V") (class "Default")
      (node (ref "C55") (pin "1") (pinfunction "1_1") (pintype "passive"))
      (node (ref "C56") (pin "1") (pinfunction "1_1") (pintype "passive"))
      (node (ref "CR1") (pin "1") (pinfunction "1_1") (pintype "passive"))
      (node (ref "CR2") (pin "1") (pinfunction "1_1") (pintype "passive"))
      (node (ref "CR4") (pin "1") (pinfunction "1_1") (pintype "passive"))
      (node (ref "CR5") (pin "1") (pinfunction "1_1") (pintype "passive"))
      (node (ref "CR7") (pin "1") (pinfunction "1_1") (pintype "passive"))
      (node (ref "CR8") (pin "1") (pinfunction "1_1") (pintype "passive"))
      (node (ref "CW1") (pin "2") (pinfunction "2_2") (pintype "passive"))
      (node (ref "CW2") (pin "2") (pinfunction "2_2") (pintype "passive"))
      (node (ref "DR1") (pin "1") (pinfunction "A_1") (pintype "passive"))
      (node (ref "DR2") (pin "1") (pinfunction "A_1") (pintype "passive"))
      (node (ref "DR3") (pin "1") (pinfunction "A_1") (pintype "passive"))
      (node (ref "IR2101S-1") (pin "1") (pinfunction "VCC_1") (pintype "power_in"))
      (node (ref "IR2101S-2") (pin "1") (pinfunction "VCC_1") (pintype "power_in"))
      (node (ref "IR2101S-3") (pin "1") (pinfunction "VCC_1") (pintype "power_in"))
      (node (ref "LM2940-5V") (pin "1") (pinfunction "IN_1") (pintype "power_in"))
      (node (ref "LV1") (pin "2") (pinfunction "2_2") (pintype "passive"))
      (node (ref "R52") (pin "1") (pinfunction "1_1") (pintype "passive"))
    )
    (net (code "196") (name "VCC 24V IN") (class "Default")
      (node (ref "DV00") (pin "1") (pinfunction "A_1") (pintype "passive"))
      (node (ref "G1") (pin "2") (pinfunction "D_2") (pintype "passive"))
      (node (ref "G2") (pin "2") (pinfunction "D_2") (pintype "passive"))
      (node (ref "G3") (pin "2") (pinfunction "D_2") (pintype "passive"))
      (node (ref "POWER_24V") (pin "2") (pinfunction "2_2") (pintype "passive"))
    )
    (net (code "197") (name "VDDA") (class "Default")
      (node (ref "C23") (pin "1") (pinfunction "1_1") (pintype "passive"))
      (node (ref "C24") (pin "2") (pinfunction "2_2") (pintype "passive"))
      (node (ref "LB2") (pin "1") (pinfunction "1_1") (pintype "passive"))
      (node (ref "TC264D-1") (pin "42") (pinfunction "VAREF1_42") (pintype "passive"))
      (node (ref "TC264D-1") (pin "44") (pinfunction "VDDM_44") (pintype "passive"))
    )
    (net (code "198") (name "VSSA") (class "Default")
      (node (ref "C23") (pin "2") (pinfunction "2_2") (pintype "passive"))
      (node (ref "C24") (pin "1") (pinfunction "1_1") (pintype "passive"))
      (node (ref "LB3") (pin "1") (pinfunction "1_1") (pintype "passive"))
      (node (ref "TC264D-1") (pin "41") (pinfunction "VAGND1_41") (pintype "passive"))
      (node (ref "TC264D-1") (pin "43") (pinfunction "VSSM_43") (pintype "passive"))
    )
    (net (code "199") (name "unconnected-(3232-R2IN-Pad8)") (class "Default")
      (node (ref "3232") (pin "8") (pinfunction "R2IN_8") (pintype "input+no_connect"))
    )
    (net (code "200") (name "unconnected-(3232-R2OUT-Pad9)") (class "Default")
      (node (ref "3232") (pin "9") (pinfunction "R2OUT_9") (pintype "output"))
    )
    (net (code "201") (name "unconnected-(3232-T2IN-Pad10)") (class "Default")
      (node (ref "3232") (pin "10") (pinfunction "T2IN_10") (pintype "input"))
    )
    (net (code "202") (name "unconnected-(3232-T2OUT-Pad7)") (class "Default")
      (node (ref "3232") (pin "7") (pinfunction "T2OUT_7") (pintype "output+no_connect"))
    )
    (net (code "203") (name "unconnected-(LMR36520-PG-Pad4)") (class "Default")
      (node (ref "LMR36520") (pin "4") (pinfunction "PG_4") (pintype "passive+no_connect"))
    )
    (net (code "204") (name "unconnected-(R11-Pad1)") (class "Default")
      (node (ref "R11") (pin "1") (pinfunction "1_1") (pintype "passive"))
    )
    (net (code "205") (name "unconnected-(R11-Pad8)") (class "Default")
      (node (ref "R11") (pin "8") (pinfunction "8_8") (pintype "passive"))
    )
    (net (code "206") (name "unconnected-(R12-Pad1)") (class "Default")
      (node (ref "R12") (pin "1") (pinfunction "1_1") (pintype "passive"))
    )
    (net (code "207") (name "unconnected-(R12-Pad2)") (class "Default")
      (node (ref "R12") (pin "2") (pinfunction "2_2") (pintype "passive"))
    )
    (net (code "208") (name "unconnected-(R12-Pad7)") (class "Default")
      (node (ref "R12") (pin "7") (pinfunction "7_7") (pintype "passive"))
    )
    (net (code "209") (name "unconnected-(R12-Pad8)") (class "Default")
      (node (ref "R12") (pin "8") (pinfunction "8_8") (pintype "passive"))
    )
    (net (code "210") (name "unconnected-(RM2-Pad1)") (class "Default")
      (node (ref "RM2") (pin "1") (pinfunction "1_1") (pintype "passive"))
    )
    (net (code "211") (name "unconnected-(TC264D-1-ESR0#-Pad98)") (class "Default")
      (node (ref "TC264D-1") (pin "98") (pinfunction "ESR0#_98") (pintype "passive"))
    )
    (net (code "212") (name "unconnected-(TC264D-1-ESR1#-Pad96)") (class "Default")
      (node (ref "TC264D-1") (pin "96") (pinfunction "ESR1#_96") (pintype "passive"))
    )
    (net (code "213") (name "unconnected-(TC264D-1-P20_0-Pad93)") (class "Default")
      (node (ref "TC264D-1") (pin "93") (pinfunction "P20_0_93") (pintype "passive"))
    )
    (net (code "214") (name "unconnected-(TC264D-1-P21_6{slash}TDI-Pad88)") (class "Default")
      (node (ref "TC264D-1") (pin "88") (pinfunction "P21_6/TDI_88") (pintype "passive"))
    )
  )
)
